# axiom_beta_interface_dummy_v0_13_r1_5_1a.net
KiCad netlist of a schematic drawn in EAGLE
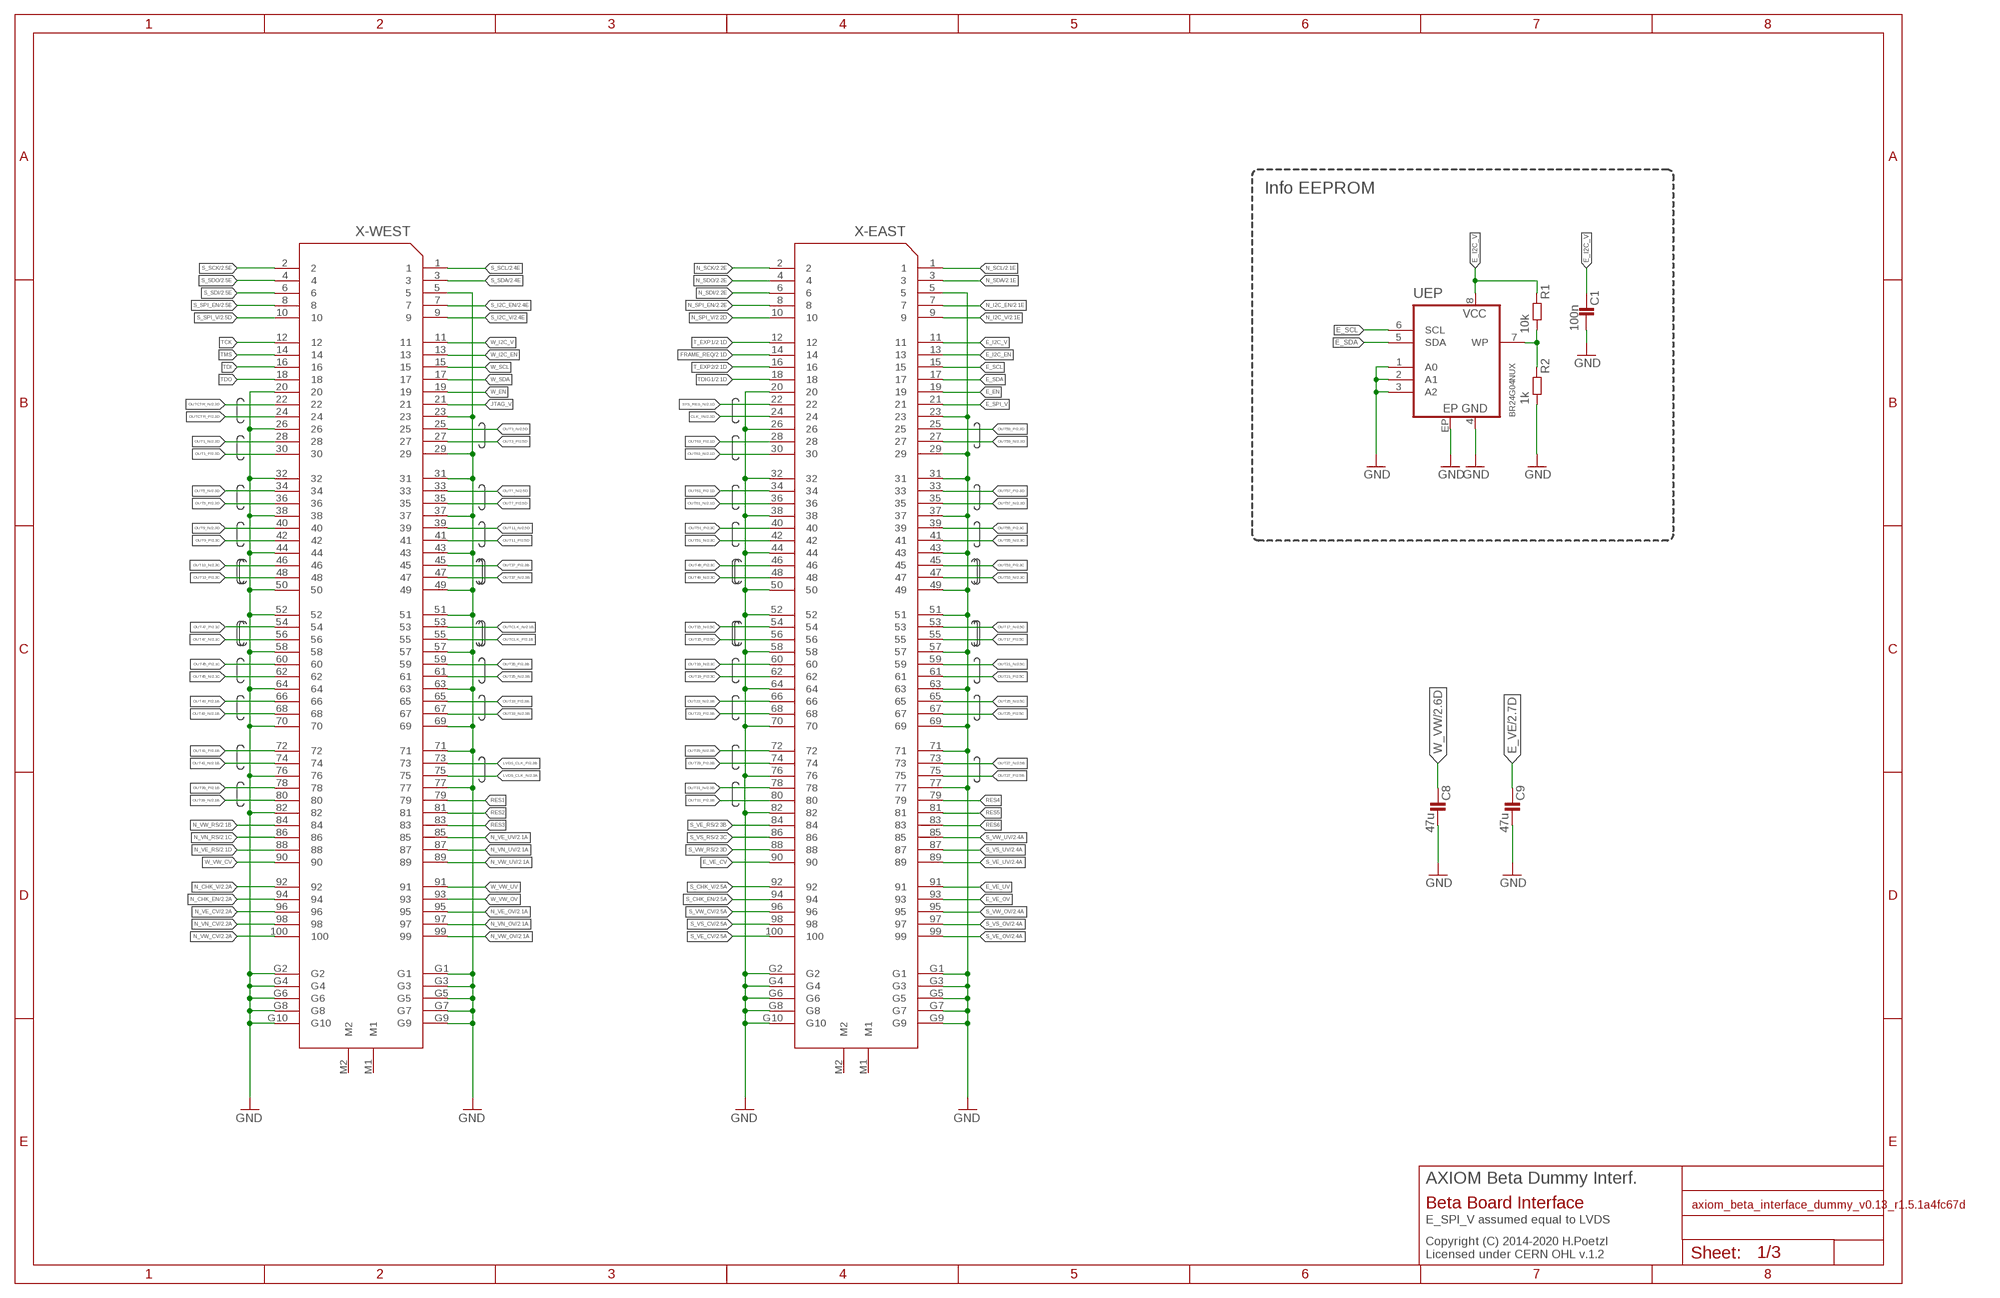
[diagram p0: schematic, sheet 1]
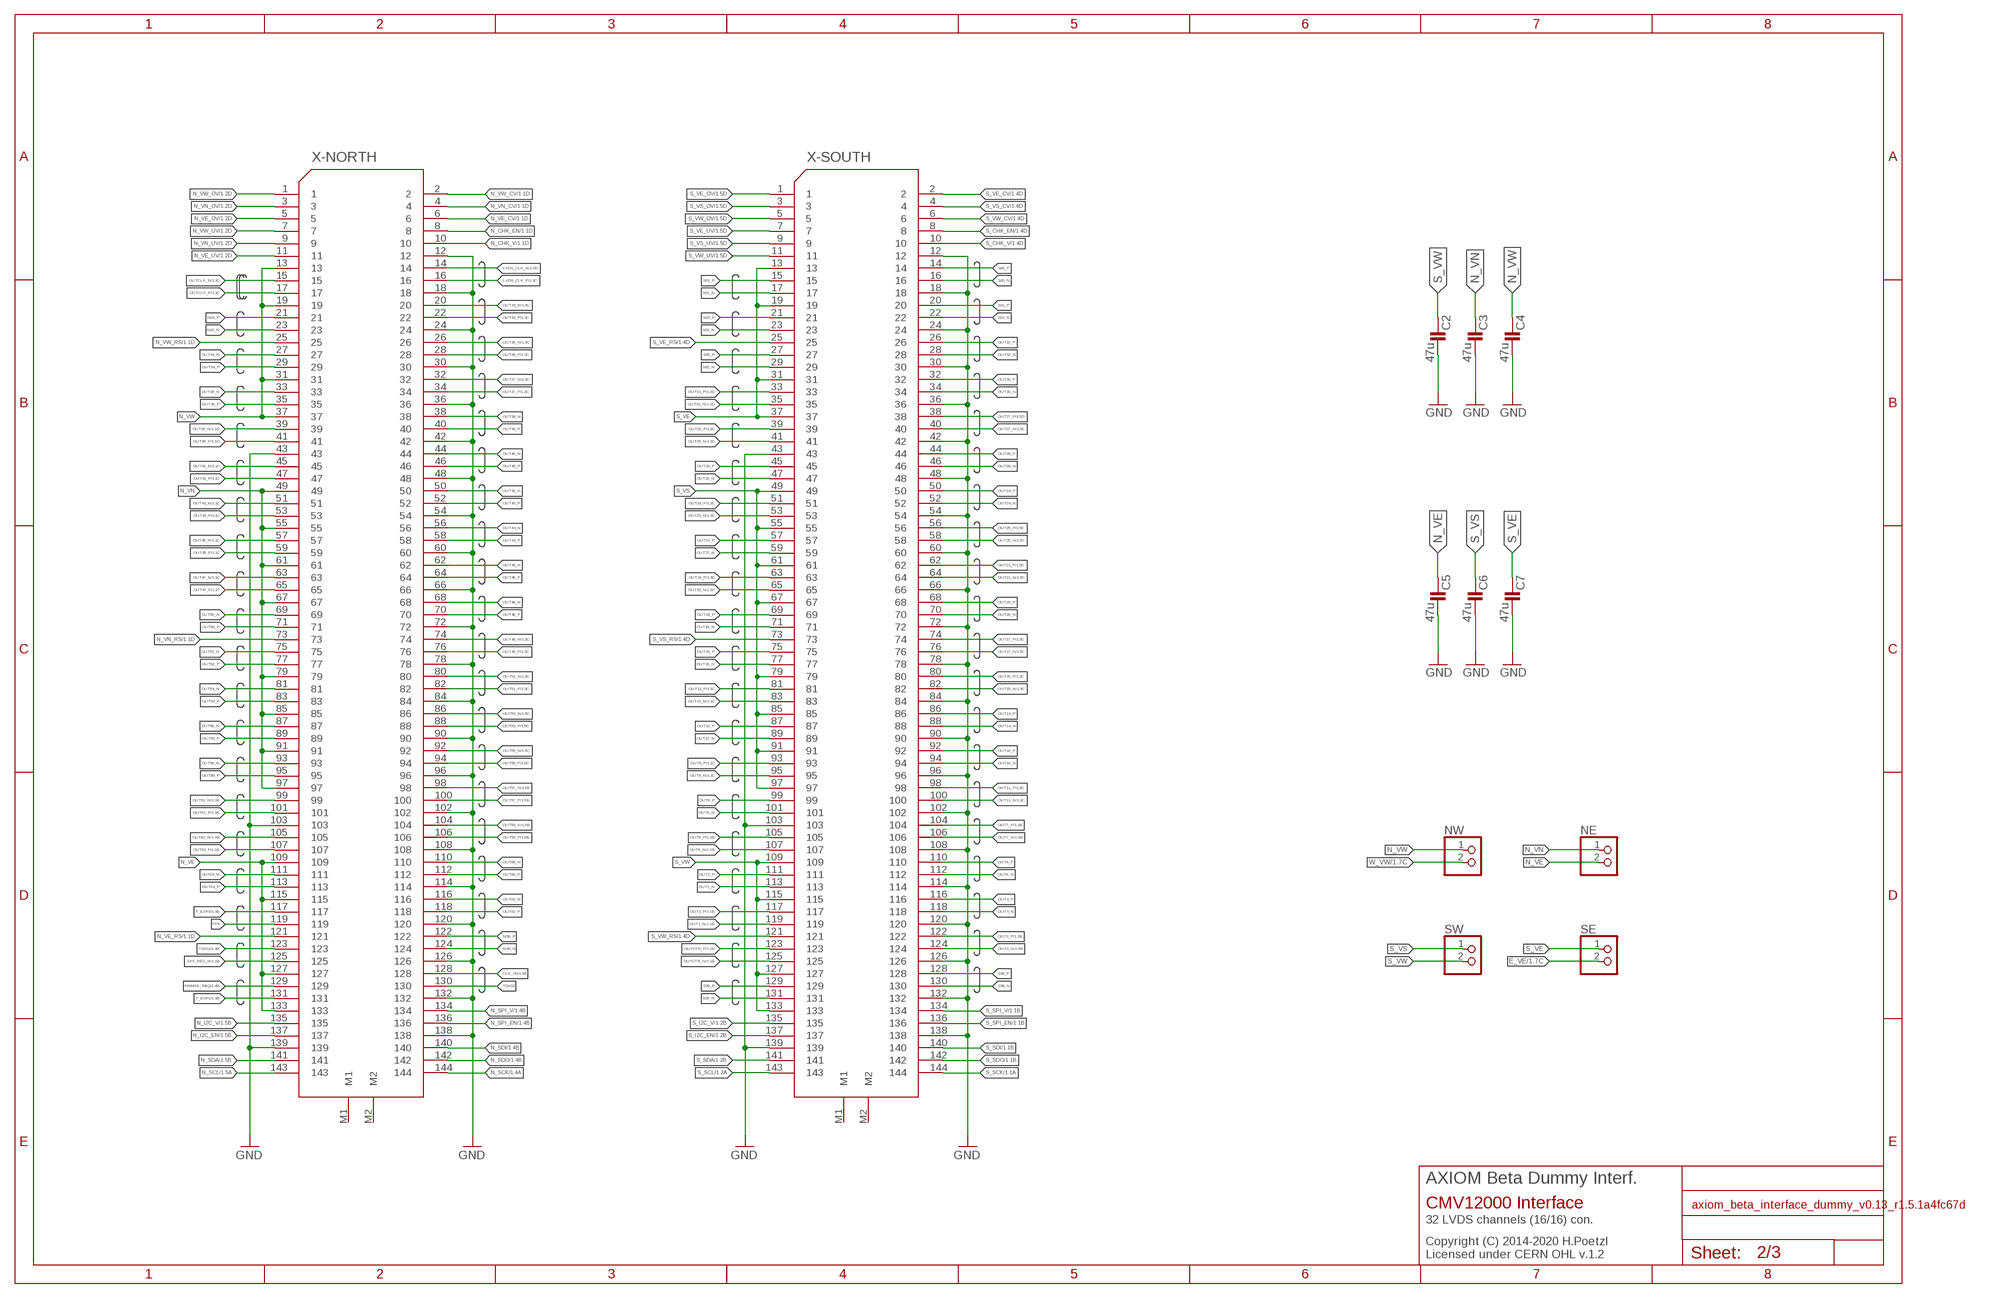
[diagram p1: schematic, sheet 2]
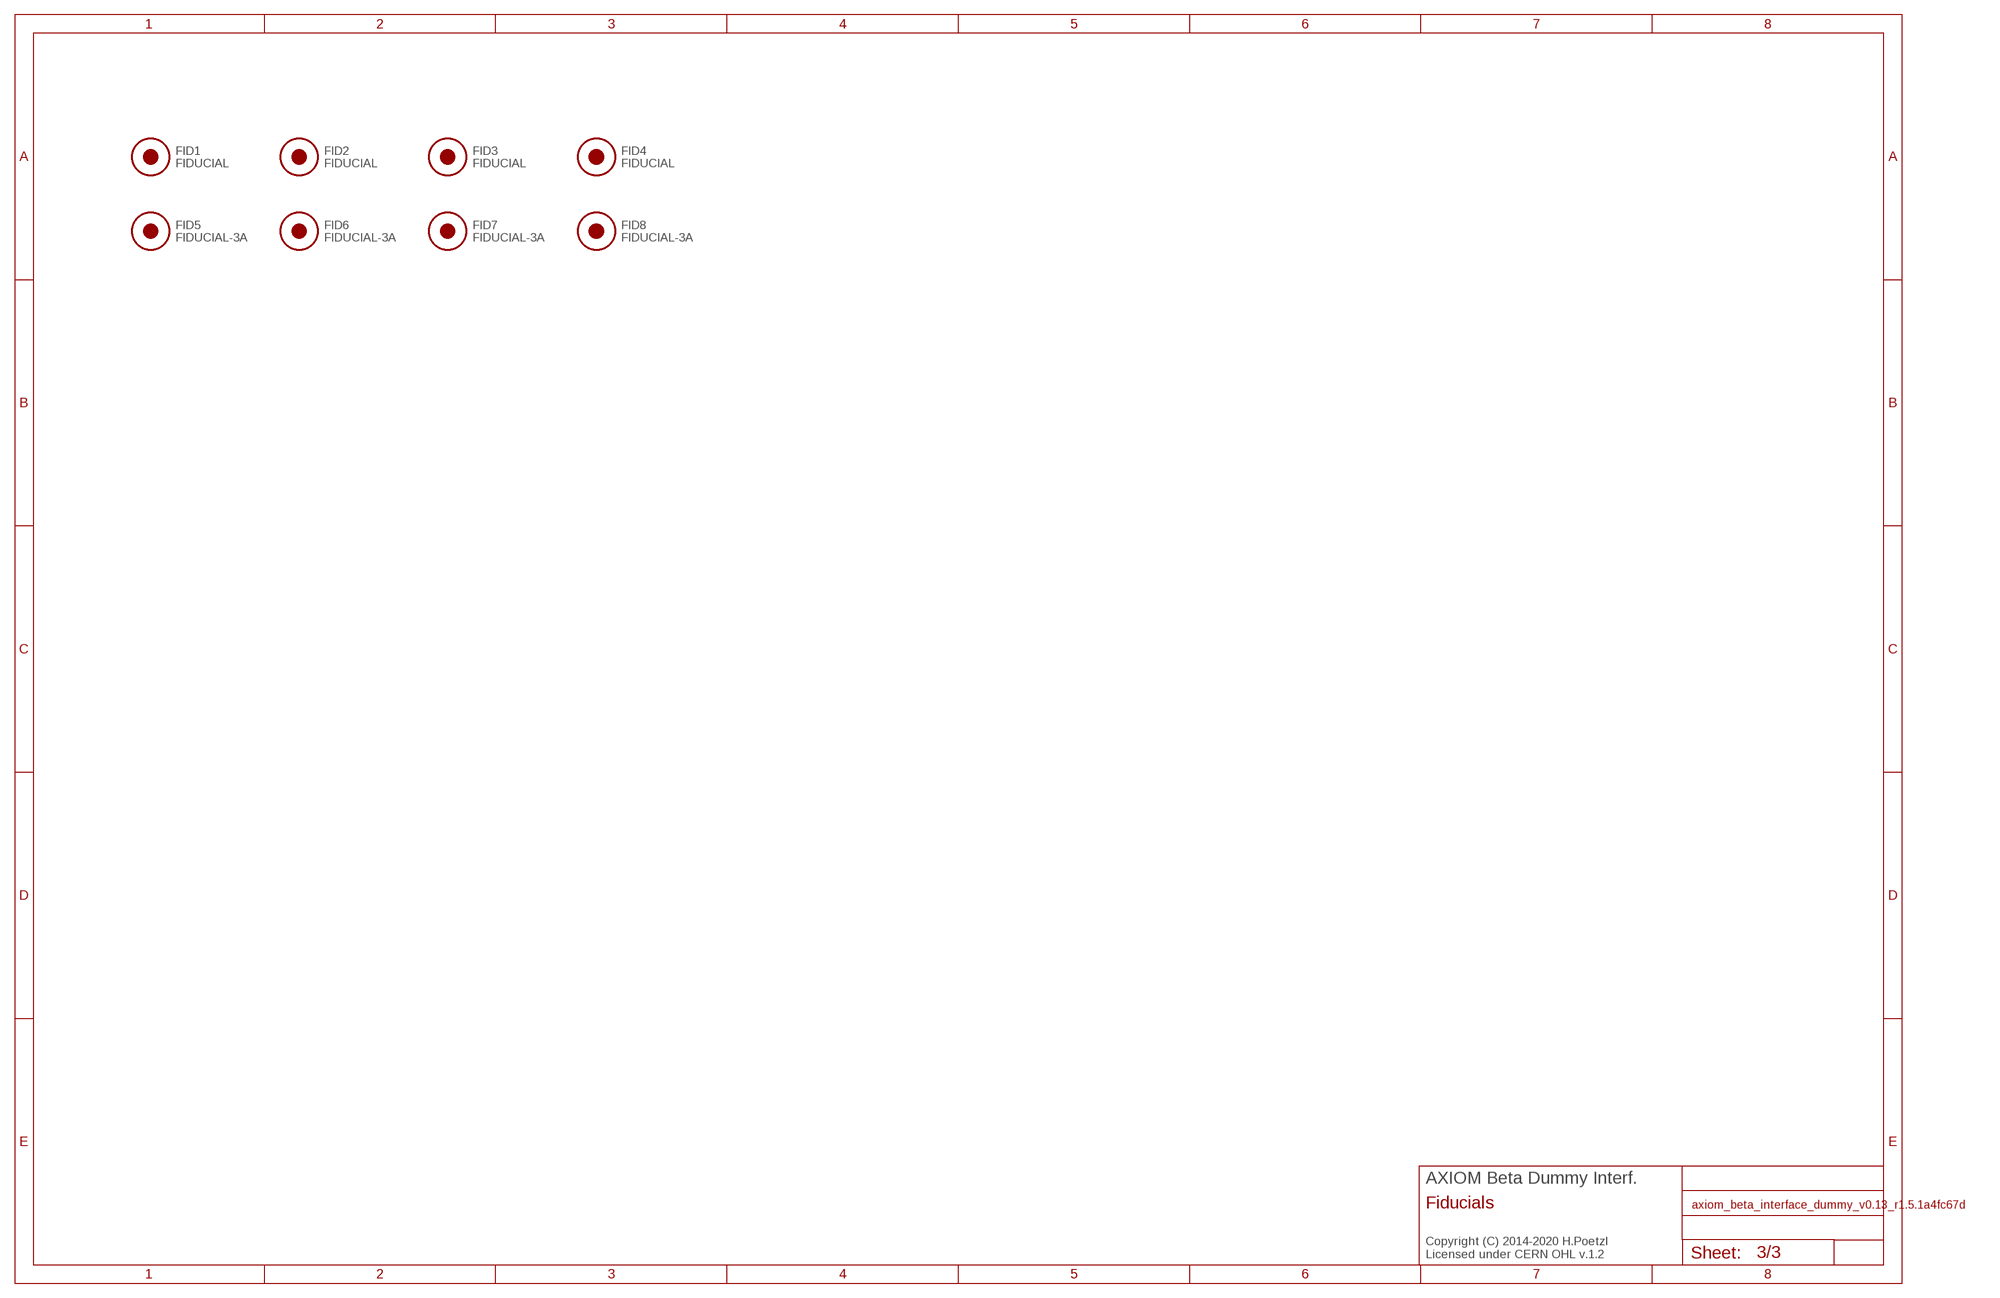
[diagram p2: schematic, sheet 3]

(export (version "E")
  (design (tool "Eeschema 10.0.6"))
  (components
    (comp (ref "FID1")
      (value "FIDUCIAL")
      (footprint "eagle-import:FID_ARROW")
      (libsource (lib "eagle-import") (part "FIDUCIAL"))
    )
    (comp (ref "FID2")
      (value "FIDUCIAL")
      (footprint "eagle-import:FID_ARROW")
      (libsource (lib "eagle-import") (part "FIDUCIAL"))
    )
    (comp (ref "FID3")
      (value "FIDUCIAL")
      (footprint "eagle-import:FID_ARROW")
      (libsource (lib "eagle-import") (part "FIDUCIAL"))
    )
    (comp (ref "FID4")
      (value "FIDUCIAL")
      (footprint "eagle-import:FID_ARROW")
      (libsource (lib "eagle-import") (part "FIDUCIAL"))
    )
    (comp (ref "FID5")
      (value "FIDUCIAL-3A")
      (footprint "eagle-import:FID_3ARROW")
      (libsource (lib "eagle-import") (part "FIDUCIAL-3A"))
    )
    (comp (ref "FID6")
      (value "FIDUCIAL-3A")
      (footprint "eagle-import:FID_3ARROW")
      (libsource (lib "eagle-import") (part "FIDUCIAL-3A"))
    )
    (comp (ref "FID7")
      (value "FIDUCIAL-3A")
      (footprint "eagle-import:FID_3ARROW")
      (libsource (lib "eagle-import") (part "FIDUCIAL-3A"))
    )
    (comp (ref "FID8")
      (value "FIDUCIAL-3A")
      (footprint "eagle-import:FID_3ARROW")
      (libsource (lib "eagle-import") (part "FIDUCIAL-3A"))
    )
    (comp (ref "C2")
      (value "47u")
      (footprint "eagle-import:0805-B")
      (libsource (lib "eagle-import") (part "C0805-B"))
    )
    (comp (ref "C3")
      (value "47u")
      (footprint "eagle-import:0805-B")
      (libsource (lib "eagle-import") (part "C0805-B"))
    )
    (comp (ref "C4")
      (value "47u")
      (footprint "eagle-import:0805-B")
      (libsource (lib "eagle-import") (part "C0805-B"))
    )
    (comp (ref "C5")
      (value "47u")
      (footprint "eagle-import:0805-B")
      (libsource (lib "eagle-import") (part "C0805-B"))
    )
    (comp (ref "C6")
      (value "47u")
      (footprint "eagle-import:0805-B")
      (libsource (lib "eagle-import") (part "C0805-B"))
    )
    (comp (ref "C7")
      (value "47u")
      (footprint "eagle-import:0805-B")
      (libsource (lib "eagle-import") (part "C0805-B"))
    )
    (comp (ref "NE")
      (value "PINHD-1X02_2.54")
      (footprint "eagle-import:1X02")
      (libsource (lib "eagle-import") (part "PINHD-1X02_2.54"))
    )
    (comp (ref "NW")
      (value "PINHD-1X02_2.54")
      (footprint "eagle-import:1X02")
      (libsource (lib "eagle-import") (part "PINHD-1X02_2.54"))
    )
    (comp (ref "SE")
      (value "PINHD-1X02_2.54")
      (footprint "eagle-import:1X02")
      (libsource (lib "eagle-import") (part "PINHD-1X02_2.54"))
    )
    (comp (ref "SW")
      (value "PINHD-1X02_2.54")
      (footprint "eagle-import:1X02")
      (libsource (lib "eagle-import") (part "PINHD-1X02_2.54"))
    )
    (comp (ref "X-NORTH")
      (value "FX10-144S")
      (footprint "eagle-import:FX10A-144S")
      (libsource (lib "eagle-import") (part "FX10-144S"))
    )
    (comp (ref "X-SOUTH")
      (value "FX10-144S")
      (footprint "eagle-import:FX10A-144S")
      (libsource (lib "eagle-import") (part "FX10-144S"))
    )
    (comp (ref "C1")
      (value "100n")
      (footprint "eagle-import:0402-B")
      (libsource (lib "eagle-import") (part "C0402-B"))
    )
    (comp (ref "C8")
      (value "47u")
      (footprint "eagle-import:0805-B")
      (libsource (lib "eagle-import") (part "C0805-B"))
    )
    (comp (ref "C9")
      (value "47u")
      (footprint "eagle-import:0805-B")
      (libsource (lib "eagle-import") (part "C0805-B"))
    )
    (comp (ref "R1")
      (value "10k")
      (footprint "eagle-import:0402-B")
      (libsource (lib "eagle-import") (part "R0402-B"))
    )
    (comp (ref "R2")
      (value "1k")
      (footprint "eagle-import:0402-B")
      (libsource (lib "eagle-import") (part "R0402-B"))
    )
    (comp (ref "UEP")
      (value "BR24G04NUX")
      (footprint "eagle-import:DFN200X300X100-9N")
      (libsource (lib "eagle-import") (part "BR24G04NUX"))
    )
    (comp (ref "X-EAST")
      (value "FX10-100/10P")
      (footprint "eagle-import:FX10A-100P_10")
      (libsource (lib "eagle-import") (part "FX10-100/10P"))
    )
    (comp (ref "X-WEST")
      (value "FX10-100/10P")
      (footprint "eagle-import:FX10A-100P_10")
      (libsource (lib "eagle-import") (part "FX10-100/10P"))
    )
  )
  (nets
    (net (code "1") (name "CLK_IN") (class "Default")
      (node (ref "X-EAST") (pin "24") (pinfunction "24_24") (pintype "bidirectional"))
      (node (ref "X-NORTH") (pin "128") (pinfunction "128_128") (pintype "bidirectional"))
    )
    (net (code "2") (name "E_EN") (class "Default")
      (node (ref "X-EAST") (pin "19") (pinfunction "19_19") (pintype "bidirectional"))
    )
    (net (code "3") (name "E_I2C_EN") (class "Default")
      (node (ref "X-EAST") (pin "13") (pinfunction "13_13") (pintype "bidirectional"))
    )
    (net (code "4") (name "E_I2C_V") (class "Default")
      (node (ref "C1") (pin "1") (pinfunction "1_1") (pintype "passive"))
      (node (ref "R1") (pin "1") (pinfunction "1_1") (pintype "passive"))
      (node (ref "UEP") (pin "8") (pinfunction "VCC_8") (pintype "power_in"))
      (node (ref "X-EAST") (pin "11") (pinfunction "11_11") (pintype "bidirectional"))
    )
    (net (code "5") (name "E_SCL") (class "Default")
      (node (ref "UEP") (pin "6") (pinfunction "SCL_6") (pintype "input"))
      (node (ref "X-EAST") (pin "15") (pinfunction "15_15") (pintype "bidirectional"))
    )
    (net (code "6") (name "E_SDA") (class "Default")
      (node (ref "UEP") (pin "5") (pinfunction "SDA_5") (pintype "bidirectional"))
      (node (ref "X-EAST") (pin "17") (pinfunction "17_17") (pintype "bidirectional"))
    )
    (net (code "7") (name "E_SPI_V") (class "Default")
      (node (ref "X-EAST") (pin "21") (pinfunction "21_21") (pintype "bidirectional"))
    )
    (net (code "8") (name "E_VE") (class "Default")
      (node (ref "C9") (pin "1") (pinfunction "1_1") (pintype "passive"))
      (node (ref "SE") (pin "2") (pinfunction "2_2") (pintype "passive"))
    )
    (net (code "9") (name "E_VE_CV") (class "Default")
      (node (ref "X-EAST") (pin "90") (pinfunction "90_90") (pintype "bidirectional"))
    )
    (net (code "10") (name "E_VE_OV") (class "Default")
      (node (ref "X-EAST") (pin "93") (pinfunction "93_93") (pintype "bidirectional"))
    )
    (net (code "11") (name "E_VE_UV") (class "Default")
      (node (ref "X-EAST") (pin "91") (pinfunction "91_91") (pintype "bidirectional"))
    )
    (net (code "12") (name "FRAME_REQ") (class "Default")
      (node (ref "X-EAST") (pin "14") (pinfunction "14_14") (pintype "bidirectional"))
      (node (ref "X-NORTH") (pin "129") (pinfunction "129_129") (pintype "bidirectional"))
    )
    (net (code "13") (name "GND") (class "Default")
      (node (ref "C1") (pin "2") (pinfunction "2_2") (pintype "passive"))
      (node (ref "C2") (pin "2") (pinfunction "2_2") (pintype "passive"))
      (node (ref "C3") (pin "2") (pinfunction "2_2") (pintype "passive"))
      (node (ref "C4") (pin "2") (pinfunction "2_2") (pintype "passive"))
      (node (ref "C5") (pin "2") (pinfunction "2_2") (pintype "passive"))
      (node (ref "C6") (pin "2") (pinfunction "2_2") (pintype "passive"))
      (node (ref "C7") (pin "2") (pinfunction "2_2") (pintype "passive"))
      (node (ref "C8") (pin "2") (pinfunction "2_2") (pintype "passive"))
      (node (ref "C9") (pin "2") (pinfunction "2_2") (pintype "passive"))
      (node (ref "R2") (pin "2") (pinfunction "2_2") (pintype "passive"))
      (node (ref "UEP") (pin "1") (pinfunction "A0_1") (pintype "input"))
      (node (ref "UEP") (pin "2") (pinfunction "A1_2") (pintype "input"))
      (node (ref "UEP") (pin "3") (pinfunction "A2_3") (pintype "input"))
      (node (ref "UEP") (pin "4") (pinfunction "GND_4") (pintype "passive"))
      (node (ref "UEP") (pin "EP") (pinfunction "EP_EP") (pintype "passive"))
      (node (ref "X-EAST") (pin "20") (pinfunction "20_20") (pintype "bidirectional"))
      (node (ref "X-EAST") (pin "23") (pinfunction "23_23") (pintype "bidirectional"))
      (node (ref "X-EAST") (pin "26") (pinfunction "26_26") (pintype "bidirectional"))
      (node (ref "X-EAST") (pin "29") (pinfunction "29_29") (pintype "bidirectional"))
      (node (ref "X-EAST") (pin "31") (pinfunction "31_31") (pintype "bidirectional"))
      (node (ref "X-EAST") (pin "32") (pinfunction "32_32") (pintype "bidirectional"))
      (node (ref "X-EAST") (pin "37") (pinfunction "37_37") (pintype "bidirectional"))
      (node (ref "X-EAST") (pin "38") (pinfunction "38_38") (pintype "bidirectional"))
      (node (ref "X-EAST") (pin "43") (pinfunction "43_43") (pintype "bidirectional"))
      (node (ref "X-EAST") (pin "44") (pinfunction "44_44") (pintype "bidirectional"))
      (node (ref "X-EAST") (pin "49") (pinfunction "49_49") (pintype "bidirectional"))
      (node (ref "X-EAST") (pin "5") (pinfunction "5_5") (pintype "bidirectional"))
      (node (ref "X-EAST") (pin "50") (pinfunction "50_50") (pintype "bidirectional"))
      (node (ref "X-EAST") (pin "51") (pinfunction "51_51") (pintype "bidirectional"))
      (node (ref "X-EAST") (pin "52") (pinfunction "52_52") (pintype "bidirectional"))
      (node (ref "X-EAST") (pin "57") (pinfunction "57_57") (pintype "bidirectional"))
      (node (ref "X-EAST") (pin "58") (pinfunction "58_58") (pintype "bidirectional"))
      (node (ref "X-EAST") (pin "63") (pinfunction "63_63") (pintype "bidirectional"))
      (node (ref "X-EAST") (pin "64") (pinfunction "64_64") (pintype "bidirectional"))
      (node (ref "X-EAST") (pin "69") (pinfunction "69_69") (pintype "bidirectional"))
      (node (ref "X-EAST") (pin "70") (pinfunction "70_70") (pintype "bidirectional"))
      (node (ref "X-EAST") (pin "71") (pinfunction "71_71") (pintype "bidirectional"))
      (node (ref "X-EAST") (pin "76") (pinfunction "76_76") (pintype "bidirectional"))
      (node (ref "X-EAST") (pin "77") (pinfunction "77_77") (pintype "bidirectional"))
      (node (ref "X-EAST") (pin "82") (pinfunction "82_82") (pintype "bidirectional"))
      (node (ref "X-EAST") (pin "G1") (pinfunction "G1_G1") (pintype "bidirectional"))
      (node (ref "X-EAST") (pin "G10") (pinfunction "G10_G10") (pintype "bidirectional"))
      (node (ref "X-EAST") (pin "G2") (pinfunction "G2_G2") (pintype "bidirectional"))
      (node (ref "X-EAST") (pin "G3") (pinfunction "G3_G3") (pintype "bidirectional"))
      (node (ref "X-EAST") (pin "G4") (pinfunction "G4_G4") (pintype "bidirectional"))
      (node (ref "X-EAST") (pin "G5") (pinfunction "G5_G5") (pintype "bidirectional"))
      (node (ref "X-EAST") (pin "G6") (pinfunction "G6_G6") (pintype "bidirectional"))
      (node (ref "X-EAST") (pin "G7") (pinfunction "G7_G7") (pintype "bidirectional"))
      (node (ref "X-EAST") (pin "G8") (pinfunction "G8_G8") (pintype "bidirectional"))
      (node (ref "X-EAST") (pin "G9") (pinfunction "G9_G9") (pintype "bidirectional"))
      (node (ref "X-NORTH") (pin "102") (pinfunction "102_102") (pintype "bidirectional"))
      (node (ref "X-NORTH") (pin "103") (pinfunction "103_103") (pintype "bidirectional"))
      (node (ref "X-NORTH") (pin "108") (pinfunction "108_108") (pintype "bidirectional"))
      (node (ref "X-NORTH") (pin "114") (pinfunction "114_114") (pintype "bidirectional"))
      (node (ref "X-NORTH") (pin "12") (pinfunction "12_12") (pintype "bidirectional"))
      (node (ref "X-NORTH") (pin "120") (pinfunction "120_120") (pintype "bidirectional"))
      (node (ref "X-NORTH") (pin "126") (pinfunction "126_126") (pintype "bidirectional"))
      (node (ref "X-NORTH") (pin "132") (pinfunction "132_132") (pintype "bidirectional"))
      (node (ref "X-NORTH") (pin "138") (pinfunction "138_138") (pintype "bidirectional"))
      (node (ref "X-NORTH") (pin "139") (pinfunction "139_139") (pintype "bidirectional"))
      (node (ref "X-NORTH") (pin "18") (pinfunction "18_18") (pintype "bidirectional"))
      (node (ref "X-NORTH") (pin "24") (pinfunction "24_24") (pintype "bidirectional"))
      (node (ref "X-NORTH") (pin "30") (pinfunction "30_30") (pintype "bidirectional"))
      (node (ref "X-NORTH") (pin "36") (pinfunction "36_36") (pintype "bidirectional"))
      (node (ref "X-NORTH") (pin "42") (pinfunction "42_42") (pintype "bidirectional"))
      (node (ref "X-NORTH") (pin "43") (pinfunction "43_43") (pintype "bidirectional"))
      (node (ref "X-NORTH") (pin "48") (pinfunction "48_48") (pintype "bidirectional"))
      (node (ref "X-NORTH") (pin "54") (pinfunction "54_54") (pintype "bidirectional"))
      (node (ref "X-NORTH") (pin "60") (pinfunction "60_60") (pintype "bidirectional"))
      (node (ref "X-NORTH") (pin "66") (pinfunction "66_66") (pintype "bidirectional"))
      (node (ref "X-NORTH") (pin "72") (pinfunction "72_72") (pintype "bidirectional"))
      (node (ref "X-NORTH") (pin "78") (pinfunction "78_78") (pintype "bidirectional"))
      (node (ref "X-NORTH") (pin "84") (pinfunction "84_84") (pintype "bidirectional"))
      (node (ref "X-NORTH") (pin "90") (pinfunction "90_90") (pintype "bidirectional"))
      (node (ref "X-NORTH") (pin "96") (pinfunction "96_96") (pintype "bidirectional"))
      (node (ref "X-SOUTH") (pin "102") (pinfunction "102_102") (pintype "bidirectional"))
      (node (ref "X-SOUTH") (pin "103") (pinfunction "103_103") (pintype "bidirectional"))
      (node (ref "X-SOUTH") (pin "108") (pinfunction "108_108") (pintype "bidirectional"))
      (node (ref "X-SOUTH") (pin "114") (pinfunction "114_114") (pintype "bidirectional"))
      (node (ref "X-SOUTH") (pin "12") (pinfunction "12_12") (pintype "bidirectional"))
      (node (ref "X-SOUTH") (pin "120") (pinfunction "120_120") (pintype "bidirectional"))
      (node (ref "X-SOUTH") (pin "126") (pinfunction "126_126") (pintype "bidirectional"))
      (node (ref "X-SOUTH") (pin "132") (pinfunction "132_132") (pintype "bidirectional"))
      (node (ref "X-SOUTH") (pin "138") (pinfunction "138_138") (pintype "bidirectional"))
      (node (ref "X-SOUTH") (pin "139") (pinfunction "139_139") (pintype "bidirectional"))
      (node (ref "X-SOUTH") (pin "18") (pinfunction "18_18") (pintype "bidirectional"))
      (node (ref "X-SOUTH") (pin "24") (pinfunction "24_24") (pintype "bidirectional"))
      (node (ref "X-SOUTH") (pin "30") (pinfunction "30_30") (pintype "bidirectional"))
      (node (ref "X-SOUTH") (pin "36") (pinfunction "36_36") (pintype "bidirectional"))
      (node (ref "X-SOUTH") (pin "42") (pinfunction "42_42") (pintype "bidirectional"))
      (node (ref "X-SOUTH") (pin "43") (pinfunction "43_43") (pintype "bidirectional"))
      (node (ref "X-SOUTH") (pin "48") (pinfunction "48_48") (pintype "bidirectional"))
      (node (ref "X-SOUTH") (pin "54") (pinfunction "54_54") (pintype "bidirectional"))
      (node (ref "X-SOUTH") (pin "60") (pinfunction "60_60") (pintype "bidirectional"))
      (node (ref "X-SOUTH") (pin "66") (pinfunction "66_66") (pintype "bidirectional"))
      (node (ref "X-SOUTH") (pin "72") (pinfunction "72_72") (pintype "bidirectional"))
      (node (ref "X-SOUTH") (pin "78") (pinfunction "78_78") (pintype "bidirectional"))
      (node (ref "X-SOUTH") (pin "84") (pinfunction "84_84") (pintype "bidirectional"))
      (node (ref "X-SOUTH") (pin "90") (pinfunction "90_90") (pintype "bidirectional"))
      (node (ref "X-SOUTH") (pin "96") (pinfunction "96_96") (pintype "bidirectional"))
      (node (ref "X-WEST") (pin "20") (pinfunction "20_20") (pintype "bidirectional"))
      (node (ref "X-WEST") (pin "23") (pinfunction "23_23") (pintype "bidirectional"))
      (node (ref "X-WEST") (pin "26") (pinfunction "26_26") (pintype "bidirectional"))
      (node (ref "X-WEST") (pin "29") (pinfunction "29_29") (pintype "bidirectional"))
      (node (ref "X-WEST") (pin "31") (pinfunction "31_31") (pintype "bidirectional"))
      (node (ref "X-WEST") (pin "32") (pinfunction "32_32") (pintype "bidirectional"))
      (node (ref "X-WEST") (pin "37") (pinfunction "37_37") (pintype "bidirectional"))
      (node (ref "X-WEST") (pin "38") (pinfunction "38_38") (pintype "bidirectional"))
      (node (ref "X-WEST") (pin "43") (pinfunction "43_43") (pintype "bidirectional"))
      (node (ref "X-WEST") (pin "44") (pinfunction "44_44") (pintype "bidirectional"))
      (node (ref "X-WEST") (pin "49") (pinfunction "49_49") (pintype "bidirectional"))
      (node (ref "X-WEST") (pin "5") (pinfunction "5_5") (pintype "bidirectional"))
      (node (ref "X-WEST") (pin "50") (pinfunction "50_50") (pintype "bidirectional"))
      (node (ref "X-WEST") (pin "51") (pinfunction "51_51") (pintype "bidirectional"))
      (node (ref "X-WEST") (pin "52") (pinfunction "52_52") (pintype "bidirectional"))
      (node (ref "X-WEST") (pin "57") (pinfunction "57_57") (pintype "bidirectional"))
      (node (ref "X-WEST") (pin "58") (pinfunction "58_58") (pintype "bidirectional"))
      (node (ref "X-WEST") (pin "63") (pinfunction "63_63") (pintype "bidirectional"))
      (node (ref "X-WEST") (pin "64") (pinfunction "64_64") (pintype "bidirectional"))
      (node (ref "X-WEST") (pin "69") (pinfunction "69_69") (pintype "bidirectional"))
      (node (ref "X-WEST") (pin "70") (pinfunction "70_70") (pintype "bidirectional"))
      (node (ref "X-WEST") (pin "71") (pinfunction "71_71") (pintype "bidirectional"))
      (node (ref "X-WEST") (pin "76") (pinfunction "76_76") (pintype "bidirectional"))
      (node (ref "X-WEST") (pin "77") (pinfunction "77_77") (pintype "bidirectional"))
      (node (ref "X-WEST") (pin "82") (pinfunction "82_82") (pintype "bidirectional"))
      (node (ref "X-WEST") (pin "G1") (pinfunction "G1_G1") (pintype "bidirectional"))
      (node (ref "X-WEST") (pin "G10") (pinfunction "G10_G10") (pintype "bidirectional"))
      (node (ref "X-WEST") (pin "G2") (pinfunction "G2_G2") (pintype "bidirectional"))
      (node (ref "X-WEST") (pin "G3") (pinfunction "G3_G3") (pintype "bidirectional"))
      (node (ref "X-WEST") (pin "G4") (pinfunction "G4_G4") (pintype "bidirectional"))
      (node (ref "X-WEST") (pin "G5") (pinfunction "G5_G5") (pintype "bidirectional"))
      (node (ref "X-WEST") (pin "G6") (pinfunction "G6_G6") (pintype "bidirectional"))
      (node (ref "X-WEST") (pin "G7") (pinfunction "G7_G7") (pintype "bidirectional"))
      (node (ref "X-WEST") (pin "G8") (pinfunction "G8_G8") (pintype "bidirectional"))
      (node (ref "X-WEST") (pin "G9") (pinfunction "G9_G9") (pintype "bidirectional"))
    )
    (net (code "14") (name "JTAG_V") (class "Default")
      (node (ref "X-WEST") (pin "21") (pinfunction "21_21") (pintype "bidirectional"))
    )
    (net (code "15") (name "LVDS_CLK_N") (class "Default")
      (node (ref "X-NORTH") (pin "14") (pinfunction "14_14") (pintype "bidirectional"))
      (node (ref "X-WEST") (pin "75") (pinfunction "75_75") (pintype "bidirectional"))
    )
    (net (code "16") (name "LVDS_CLK_P") (class "Default")
      (node (ref "X-NORTH") (pin "16") (pinfunction "16_16") (pintype "bidirectional"))
      (node (ref "X-WEST") (pin "73") (pinfunction "73_73") (pintype "bidirectional"))
    )
    (net (code "17") (name "N03_N") (class "Default")
      (node (ref "X-NORTH") (pin "23") (pinfunction "23_23") (pintype "bidirectional"))
    )
    (net (code "18") (name "N03_P") (class "Default")
      (node (ref "X-NORTH") (pin "21") (pinfunction "21_21") (pintype "bidirectional"))
    )
    (net (code "19") (name "N36_N") (class "Default")
      (node (ref "X-NORTH") (pin "124") (pinfunction "124_124") (pintype "bidirectional"))
    )
    (net (code "20") (name "N36_P") (class "Default")
      (node (ref "X-NORTH") (pin "122") (pinfunction "122_122") (pintype "bidirectional"))
    )
    (net (code "21") (name "N_CHK_EN") (class "Default")
      (node (ref "X-NORTH") (pin "8") (pinfunction "8_8") (pintype "bidirectional"))
      (node (ref "X-WEST") (pin "94") (pinfunction "94_94") (pintype "bidirectional"))
    )
    (net (code "22") (name "N_CHK_V") (class "Default")
      (node (ref "X-NORTH") (pin "10") (pinfunction "10_10") (pintype "bidirectional"))
      (node (ref "X-WEST") (pin "92") (pinfunction "92_92") (pintype "bidirectional"))
    )
    (net (code "23") (name "N_I2C_EN") (class "Default")
      (node (ref "X-EAST") (pin "7") (pinfunction "7_7") (pintype "bidirectional"))
      (node (ref "X-NORTH") (pin "137") (pinfunction "137_137") (pintype "bidirectional"))
    )
    (net (code "24") (name "N_I2C_V") (class "Default")
      (node (ref "X-EAST") (pin "9") (pinfunction "9_9") (pintype "bidirectional"))
      (node (ref "X-NORTH") (pin "135") (pinfunction "135_135") (pintype "bidirectional"))
    )
    (net (code "25") (name "N_SCK") (class "Default")
      (node (ref "X-EAST") (pin "2") (pinfunction "2_2") (pintype "bidirectional"))
      (node (ref "X-NORTH") (pin "144") (pinfunction "144_144") (pintype "bidirectional"))
    )
    (net (code "26") (name "N_SCL") (class "Default")
      (node (ref "X-EAST") (pin "1") (pinfunction "1_1") (pintype "bidirectional"))
      (node (ref "X-NORTH") (pin "143") (pinfunction "143_143") (pintype "bidirectional"))
    )
    (net (code "27") (name "N_SDA") (class "Default")
      (node (ref "X-EAST") (pin "3") (pinfunction "3_3") (pintype "bidirectional"))
      (node (ref "X-NORTH") (pin "141") (pinfunction "141_141") (pintype "bidirectional"))
    )
    (net (code "28") (name "N_SDI") (class "Default")
      (node (ref "X-EAST") (pin "6") (pinfunction "6_6") (pintype "bidirectional"))
      (node (ref "X-NORTH") (pin "140") (pinfunction "140_140") (pintype "bidirectional"))
    )
    (net (code "29") (name "N_SDO") (class "Default")
      (node (ref "X-EAST") (pin "4") (pinfunction "4_4") (pintype "bidirectional"))
      (node (ref "X-NORTH") (pin "142") (pinfunction "142_142") (pintype "bidirectional"))
    )
    (net (code "30") (name "N_SPI_EN") (class "Default")
      (node (ref "X-EAST") (pin "8") (pinfunction "8_8") (pintype "bidirectional"))
      (node (ref "X-NORTH") (pin "136") (pinfunction "136_136") (pintype "bidirectional"))
    )
    (net (code "31") (name "N_SPI_V") (class "Default")
      (node (ref "X-EAST") (pin "10") (pinfunction "10_10") (pintype "bidirectional"))
      (node (ref "X-NORTH") (pin "134") (pinfunction "134_134") (pintype "bidirectional"))
    )
    (net (code "32") (name "N_VE") (class "Default")
      (node (ref "C5") (pin "1") (pinfunction "1_1") (pintype "passive"))
      (node (ref "NE") (pin "2") (pinfunction "2_2") (pintype "passive"))
      (node (ref "X-NORTH") (pin "109") (pinfunction "109_109") (pintype "bidirectional"))
      (node (ref "X-NORTH") (pin "115") (pinfunction "115_115") (pintype "bidirectional"))
      (node (ref "X-NORTH") (pin "127") (pinfunction "127_127") (pintype "bidirectional"))
      (node (ref "X-NORTH") (pin "133") (pinfunction "133_133") (pintype "bidirectional"))
    )
    (net (code "33") (name "N_VE_CV") (class "Default")
      (node (ref "X-NORTH") (pin "6") (pinfunction "6_6") (pintype "bidirectional"))
      (node (ref "X-WEST") (pin "96") (pinfunction "96_96") (pintype "bidirectional"))
    )
    (net (code "34") (name "N_VE_OV") (class "Default")
      (node (ref "X-NORTH") (pin "5") (pinfunction "5_5") (pintype "bidirectional"))
      (node (ref "X-WEST") (pin "95") (pinfunction "95_95") (pintype "bidirectional"))
    )
    (net (code "35") (name "N_VE_RS") (class "Default")
      (node (ref "X-NORTH") (pin "121") (pinfunction "121_121") (pintype "bidirectional"))
      (node (ref "X-WEST") (pin "88") (pinfunction "88_88") (pintype "bidirectional"))
    )
    (net (code "36") (name "N_VE_UV") (class "Default")
      (node (ref "X-NORTH") (pin "11") (pinfunction "11_11") (pintype "bidirectional"))
      (node (ref "X-WEST") (pin "85") (pinfunction "85_85") (pintype "bidirectional"))
    )
    (net (code "37") (name "N_VN") (class "Default")
      (node (ref "C3") (pin "1") (pinfunction "1_1") (pintype "passive"))
      (node (ref "NE") (pin "1") (pinfunction "1_1") (pintype "passive"))
      (node (ref "X-NORTH") (pin "49") (pinfunction "49_49") (pintype "bidirectional"))
      (node (ref "X-NORTH") (pin "55") (pinfunction "55_55") (pintype "bidirectional"))
      (node (ref "X-NORTH") (pin "61") (pinfunction "61_61") (pintype "bidirectional"))
      (node (ref "X-NORTH") (pin "67") (pinfunction "67_67") (pintype "bidirectional"))
      (node (ref "X-NORTH") (pin "79") (pinfunction "79_79") (pintype "bidirectional"))
      (node (ref "X-NORTH") (pin "85") (pinfunction "85_85") (pintype "bidirectional"))
      (node (ref "X-NORTH") (pin "91") (pinfunction "91_91") (pintype "bidirectional"))
      (node (ref "X-NORTH") (pin "97") (pinfunction "97_97") (pintype "bidirectional"))
    )
    (net (code "38") (name "N_VN_CV") (class "Default")
      (node (ref "X-NORTH") (pin "4") (pinfunction "4_4") (pintype "bidirectional"))
      (node (ref "X-WEST") (pin "98") (pinfunction "98_98") (pintype "bidirectional"))
    )
    (net (code "39") (name "N_VN_OV") (class "Default")
      (node (ref "X-NORTH") (pin "3") (pinfunction "3_3") (pintype "bidirectional"))
      (node (ref "X-WEST") (pin "97") (pinfunction "97_97") (pintype "bidirectional"))
    )
    (net (code "40") (name "N_VN_RS") (class "Default")
      (node (ref "X-NORTH") (pin "73") (pinfunction "73_73") (pintype "bidirectional"))
      (node (ref "X-WEST") (pin "86") (pinfunction "86_86") (pintype "bidirectional"))
    )
    (net (code "41") (name "N_VN_UV") (class "Default")
      (node (ref "X-NORTH") (pin "9") (pinfunction "9_9") (pintype "bidirectional"))
      (node (ref "X-WEST") (pin "87") (pinfunction "87_87") (pintype "bidirectional"))
    )
    (net (code "42") (name "N_VW") (class "Default")
      (node (ref "C4") (pin "1") (pinfunction "1_1") (pintype "passive"))
      (node (ref "NW") (pin "1") (pinfunction "1_1") (pintype "passive"))
      (node (ref "X-NORTH") (pin "13") (pinfunction "13_13") (pintype "bidirectional"))
      (node (ref "X-NORTH") (pin "19") (pinfunction "19_19") (pintype "bidirectional"))
      (node (ref "X-NORTH") (pin "31") (pinfunction "31_31") (pintype "bidirectional"))
      (node (ref "X-NORTH") (pin "37") (pinfunction "37_37") (pintype "bidirectional"))
    )
    (net (code "43") (name "N_VW_CV") (class "Default")
      (node (ref "X-NORTH") (pin "2") (pinfunction "2_2") (pintype "bidirectional"))
      (node (ref "X-WEST") (pin "100") (pinfunction "100_100") (pintype "bidirectional"))
    )
    (net (code "44") (name "N_VW_OV") (class "Default")
      (node (ref "X-NORTH") (pin "1") (pinfunction "1_1") (pintype "bidirectional"))
      (node (ref "X-WEST") (pin "99") (pinfunction "99_99") (pintype "bidirectional"))
    )
    (net (code "45") (name "N_VW_RS") (class "Default")
      (node (ref "X-NORTH") (pin "25") (pinfunction "25_25") (pintype "bidirectional"))
      (node (ref "X-WEST") (pin "84") (pinfunction "84_84") (pintype "bidirectional"))
    )
    (net (code "46") (name "N_VW_UV") (class "Default")
      (node (ref "X-NORTH") (pin "7") (pinfunction "7_7") (pintype "bidirectional"))
      (node (ref "X-WEST") (pin "89") (pinfunction "89_89") (pintype "bidirectional"))
    )
    (net (code "47") (name "Net-(UEP-WP)") (class "Default")
      (node (ref "R1") (pin "2") (pinfunction "2_2") (pintype "passive"))
      (node (ref "R2") (pin "1") (pinfunction "1_1") (pintype "passive"))
      (node (ref "UEP") (pin "7") (pinfunction "WP_7") (pintype "input"))
    )
    (net (code "48") (name "OUT1_N") (class "Default")
      (node (ref "X-SOUTH") (pin "119") (pinfunction "119_119") (pintype "bidirectional"))
      (node (ref "X-WEST") (pin "28") (pinfunction "28_28") (pintype "bidirectional"))
    )
    (net (code "49") (name "OUT1_P") (class "Default")
      (node (ref "X-SOUTH") (pin "117") (pinfunction "117_117") (pintype "bidirectional"))
      (node (ref "X-WEST") (pin "30") (pinfunction "30_30") (pintype "bidirectional"))
    )
    (net (code "50") (name "OUT2_N") (class "Default")
      (node (ref "X-SOUTH") (pin "113") (pinfunction "113_113") (pintype "bidirectional"))
    )
    (net (code "51") (name "OUT2_P") (class "Default")
      (node (ref "X-SOUTH") (pin "111") (pinfunction "111_111") (pintype "bidirectional"))
    )
    (net (code "52") (name "OUT3_N") (class "Default")
      (node (ref "X-SOUTH") (pin "124") (pinfunction "124_124") (pintype "bidirectional"))
      (node (ref "X-WEST") (pin "25") (pinfunction "25_25") (pintype "bidirectional"))
    )
    (net (code "53") (name "OUT3_P") (class "Default")
      (node (ref "X-SOUTH") (pin "122") (pinfunction "122_122") (pintype "bidirectional"))
      (node (ref "X-WEST") (pin "27") (pinfunction "27_27") (pintype "bidirectional"))
    )
    (net (code "54") (name "OUT4_N") (class "Default")
      (node (ref "X-SOUTH") (pin "118") (pinfunction "118_118") (pintype "bidirectional"))
    )
    (net (code "55") (name "OUT4_P") (class "Default")
      (node (ref "X-SOUTH") (pin "116") (pinfunction "116_116") (pintype "bidirectional"))
    )
    (net (code "56") (name "OUT5_N") (class "Default")
      (node (ref "X-SOUTH") (pin "107") (pinfunction "107_107") (pintype "bidirectional"))
      (node (ref "X-WEST") (pin "34") (pinfunction "34_34") (pintype "bidirectional"))
    )
    (net (code "57") (name "OUT5_P") (class "Default")
      (node (ref "X-SOUTH") (pin "105") (pinfunction "105_105") (pintype "bidirectional"))
      (node (ref "X-WEST") (pin "36") (pinfunction "36_36") (pintype "bidirectional"))
    )
    (net (code "58") (name "OUT6_N") (class "Default")
      (node (ref "X-SOUTH") (pin "112") (pinfunction "112_112") (pintype "bidirectional"))
    )
    (net (code "59") (name "OUT6_P") (class "Default")
      (node (ref "X-SOUTH") (pin "110") (pinfunction "110_110") (pintype "bidirectional"))
    )
    (net (code "60") (name "OUT7_N") (class "Default")
      (node (ref "X-SOUTH") (pin "106") (pinfunction "106_106") (pintype "bidirectional"))
      (node (ref "X-WEST") (pin "33") (pinfunction "33_33") (pintype "bidirectional"))
    )
    (net (code "61") (name "OUT7_P") (class "Default")
      (node (ref "X-SOUTH") (pin "104") (pinfunction "104_104") (pintype "bidirectional"))
      (node (ref "X-WEST") (pin "35") (pinfunction "35_35") (pintype "bidirectional"))
    )
    (net (code "62") (name "OUT8_N") (class "Default")
      (node (ref "X-SOUTH") (pin "101") (pinfunction "101_101") (pintype "bidirectional"))
    )
    (net (code "63") (name "OUT8_P") (class "Default")
      (node (ref "X-SOUTH") (pin "99") (pinfunction "99_99") (pintype "bidirectional"))
    )
    (net (code "64") (name "OUT9_N") (class "Default")
      (node (ref "X-SOUTH") (pin "95") (pinfunction "95_95") (pintype "bidirectional"))
      (node (ref "X-WEST") (pin "40") (pinfunction "40_40") (pintype "bidirectional"))
    )
    (net (code "65") (name "OUT9_P") (class "Default")
      (node (ref "X-SOUTH") (pin "93") (pinfunction "93_93") (pintype "bidirectional"))
      (node (ref "X-WEST") (pin "42") (pinfunction "42_42") (pintype "bidirectional"))
    )
    (net (code "66") (name "OUT10_N") (class "Default")
      (node (ref "X-SOUTH") (pin "94") (pinfunction "94_94") (pintype "bidirectional"))
    )
    (net (code "67") (name "OUT10_P") (class "Default")
      (node (ref "X-SOUTH") (pin "92") (pinfunction "92_92") (pintype "bidirectional"))
    )
    (net (code "68") (name "OUT11_N") (class "Default")
      (node (ref "X-SOUTH") (pin "100") (pinfunction "100_100") (pintype "bidirectional"))
      (node (ref "X-WEST") (pin "39") (pinfunction "39_39") (pintype "bidirectional"))
    )
    (net (code "69") (name "OUT11_P") (class "Default")
      (node (ref "X-SOUTH") (pin "98") (pinfunction "98_98") (pintype "bidirectional"))
      (node (ref "X-WEST") (pin "41") (pinfunction "41_41") (pintype "bidirectional"))
    )
    (net (code "70") (name "OUT12_N") (class "Default")
      (node (ref "X-SOUTH") (pin "89") (pinfunction "89_89") (pintype "bidirectional"))
    )
    (net (code "71") (name "OUT12_P") (class "Default")
      (node (ref "X-SOUTH") (pin "87") (pinfunction "87_87") (pintype "bidirectional"))
    )
    (net (code "72") (name "OUT13_N") (class "Default")
      (node (ref "X-SOUTH") (pin "83") (pinfunction "83_83") (pintype "bidirectional"))
      (node (ref "X-WEST") (pin "46") (pinfunction "46_46") (pintype "bidirectional"))
    )
    (net (code "73") (name "OUT13_P") (class "Default")
      (node (ref "X-SOUTH") (pin "81") (pinfunction "81_81") (pintype "bidirectional"))
      (node (ref "X-WEST") (pin "48") (pinfunction "48_48") (pintype "bidirectional"))
    )
    (net (code "74") (name "OUT14_N") (class "Default")
      (node (ref "X-SOUTH") (pin "88") (pinfunction "88_88") (pintype "bidirectional"))
    )
    (net (code "75") (name "OUT14_P") (class "Default")
      (node (ref "X-SOUTH") (pin "86") (pinfunction "86_86") (pintype "bidirectional"))
    )
    (net (code "76") (name "OUT15_N") (class "Default")
      (node (ref "X-EAST") (pin "54") (pinfunction "54_54") (pintype "bidirectional"))
      (node (ref "X-SOUTH") (pin "82") (pinfunction "82_82") (pintype "bidirectional"))
    )
    (net (code "77") (name "OUT15_P") (class "Default")
      (node (ref "X-EAST") (pin "56") (pinfunction "56_56") (pintype "bidirectional"))
      (node (ref "X-SOUTH") (pin "80") (pinfunction "80_80") (pintype "bidirectional"))
    )
    (net (code "78") (name "OUT16_N") (class "Default")
      (node (ref "X-SOUTH") (pin "77") (pinfunction "77_77") (pintype "bidirectional"))
    )
    (net (code "79") (name "OUT16_P") (class "Default")
      (node (ref "X-SOUTH") (pin "75") (pinfunction "75_75") (pintype "bidirectional"))
    )
    (net (code "80") (name "OUT17_N") (class "Default")
      (node (ref "X-EAST") (pin "53") (pinfunction "53_53") (pintype "bidirectional"))
      (node (ref "X-SOUTH") (pin "76") (pinfunction "76_76") (pintype "bidirectional"))
    )
    (net (code "81") (name "OUT17_P") (class "Default")
      (node (ref "X-EAST") (pin "55") (pinfunction "55_55") (pintype "bidirectional"))
      (node (ref "X-SOUTH") (pin "74") (pinfunction "74_74") (pintype "bidirectional"))
    )
    (net (code "82") (name "OUT18_N") (class "Default")
      (node (ref "X-SOUTH") (pin "71") (pinfunction "71_71") (pintype "bidirectional"))
    )
    (net (code "83") (name "OUT18_P") (class "Default")
      (node (ref "X-SOUTH") (pin "69") (pinfunction "69_69") (pintype "bidirectional"))
    )
    (net (code "84") (name "OUT19_N") (class "Default")
      (node (ref "X-EAST") (pin "60") (pinfunction "60_60") (pintype "bidirectional"))
      (node (ref "X-SOUTH") (pin "65") (pinfunction "65_65") (pintype "bidirectional"))
    )
    (net (code "85") (name "OUT19_P") (class "Default")
      (node (ref "X-EAST") (pin "62") (pinfunction "62_62") (pintype "bidirectional"))
      (node (ref "X-SOUTH") (pin "63") (pinfunction "63_63") (pintype "bidirectional"))
    )
    (net (code "86") (name "OUT20_N") (class "Default")
      (node (ref "X-SOUTH") (pin "70") (pinfunction "70_70") (pintype "bidirectional"))
    )
    (net (code "87") (name "OUT20_P") (class "Default")
      (node (ref "X-SOUTH") (pin "68") (pinfunction "68_68") (pintype "bidirectional"))
    )
    (net (code "88") (name "OUT21_N") (class "Default")
      (node (ref "X-EAST") (pin "59") (pinfunction "59_59") (pintype "bidirectional"))
      (node (ref "X-SOUTH") (pin "64") (pinfunction "64_64") (pintype "bidirectional"))
    )
    (net (code "89") (name "OUT21_P") (class "Default")
      (node (ref "X-EAST") (pin "61") (pinfunction "61_61") (pintype "bidirectional"))
      (node (ref "X-SOUTH") (pin "62") (pinfunction "62_62") (pintype "bidirectional"))
    )
    (net (code "90") (name "OUT22_N") (class "Default")
      (node (ref "X-SOUTH") (pin "59") (pinfunction "59_59") (pintype "bidirectional"))
    )
    (net (code "91") (name "OUT22_P") (class "Default")
      (node (ref "X-SOUTH") (pin "57") (pinfunction "57_57") (pintype "bidirectional"))
    )
    (net (code "92") (name "OUT23_N") (class "Default")
      (node (ref "X-EAST") (pin "66") (pinfunction "66_66") (pintype "bidirectional"))
      (node (ref "X-SOUTH") (pin "53") (pinfunction "53_53") (pintype "bidirectional"))
    )
    (net (code "93") (name "OUT23_P") (class "Default")
      (node (ref "X-EAST") (pin "68") (pinfunction "68_68") (pintype "bidirectional"))
      (node (ref "X-SOUTH") (pin "51") (pinfunction "51_51") (pintype "bidirectional"))
    )
    (net (code "94") (name "OUT24_N") (class "Default")
      (node (ref "X-SOUTH") (pin "52") (pinfunction "52_52") (pintype "bidirectional"))
    )
    (net (code "95") (name "OUT24_P") (class "Default")
      (node (ref "X-SOUTH") (pin "50") (pinfunction "50_50") (pintype "bidirectional"))
    )
    (net (code "96") (name "OUT25_N") (class "Default")
      (node (ref "X-EAST") (pin "65") (pinfunction "65_65") (pintype "bidirectional"))
      (node (ref "X-SOUTH") (pin "58") (pinfunction "58_58") (pintype "bidirectional"))
    )
    (net (code "97") (name "OUT25_P") (class "Default")
      (node (ref "X-EAST") (pin "67") (pinfunction "67_67") (pintype "bidirectional"))
      (node (ref "X-SOUTH") (pin "56") (pinfunction "56_56") (pintype "bidirectional"))
    )
    (net (code "98") (name "OUT26_N") (class "Default")
      (node (ref "X-SOUTH") (pin "47") (pinfunction "47_47") (pintype "bidirectional"))
    )
    (net (code "99") (name "OUT26_P") (class "Default")
      (node (ref "X-SOUTH") (pin "45") (pinfunction "45_45") (pintype "bidirectional"))
    )
    (net (code "100") (name "OUT27_N") (class "Default")
      (node (ref "X-EAST") (pin "73") (pinfunction "73_73") (pintype "bidirectional"))
      (node (ref "X-SOUTH") (pin "40") (pinfunction "40_40") (pintype "bidirectional"))
    )
    (net (code "101") (name "OUT27_P") (class "Default")
      (node (ref "X-EAST") (pin "75") (pinfunction "75_75") (pintype "bidirectional"))
      (node (ref "X-SOUTH") (pin "38") (pinfunction "38_38") (pintype "bidirectional"))
    )
    (net (code "102") (name "OUT28_N") (class "Default")
      (node (ref "X-SOUTH") (pin "46") (pinfunction "46_46") (pintype "bidirectional"))
    )
    (net (code "103") (name "OUT28_P") (class "Default")
      (node (ref "X-SOUTH") (pin "44") (pinfunction "44_44") (pintype "bidirectional"))
    )
    (net (code "104") (name "OUT29_N") (class "Default")
      (node (ref "X-EAST") (pin "72") (pinfunction "72_72") (pintype "bidirectional"))
      (node (ref "X-SOUTH") (pin "41") (pinfunction "41_41") (pintype "bidirectional"))
    )
    (net (code "105") (name "OUT29_P") (class "Default")
      (node (ref "X-EAST") (pin "74") (pinfunction "74_74") (pintype "bidirectional"))
      (node (ref "X-SOUTH") (pin "39") (pinfunction "39_39") (pintype "bidirectional"))
    )
    (net (code "106") (name "OUT30_N") (class "Default")
      (node (ref "X-SOUTH") (pin "34") (pinfunction "34_34") (pintype "bidirectional"))
    )
    (net (code "107") (name "OUT30_P") (class "Default")
      (node (ref "X-SOUTH") (pin "32") (pinfunction "32_32") (pintype "bidirectional"))
    )
    (net (code "108") (name "OUT31_N") (class "Default")
      (node (ref "X-EAST") (pin "78") (pinfunction "78_78") (pintype "bidirectional"))
      (node (ref "X-SOUTH") (pin "35") (pinfunction "35_35") (pintype "bidirectional"))
    )
    (net (code "109") (name "OUT31_P") (class "Default")
      (node (ref "X-EAST") (pin "80") (pinfunction "80_80") (pintype "bidirectional"))
      (node (ref "X-SOUTH") (pin "33") (pinfunction "33_33") (pintype "bidirectional"))
    )
    (net (code "110") (name "OUT32_N") (class "Default")
      (node (ref "X-SOUTH") (pin "28") (pinfunction "28_28") (pintype "bidirectional"))
    )
    (net (code "111") (name "OUT32_P") (class "Default")
      (node (ref "X-SOUTH") (pin "26") (pinfunction "26_26") (pintype "bidirectional"))
    )
    (net (code "112") (name "OUT33_N") (class "Default")
      (node (ref "X-NORTH") (pin "20") (pinfunction "20_20") (pintype "bidirectional"))
      (node (ref "X-WEST") (pin "67") (pinfunction "67_67") (pintype "bidirectional"))
    )
    (net (code "113") (name "OUT33_P") (class "Default")
      (node (ref "X-NORTH") (pin "22") (pinfunction "22_22") (pintype "bidirectional"))
      (node (ref "X-WEST") (pin "65") (pinfunction "65_65") (pintype "bidirectional"))
    )
    (net (code "114") (name "OUT34_N") (class "Default")
      (node (ref "X-NORTH") (pin "27") (pinfunction "27_27") (pintype "bidirectional"))
    )
    (net (code "115") (name "OUT34_P") (class "Default")
      (node (ref "X-NORTH") (pin "29") (pinfunction "29_29") (pintype "bidirectional"))
    )
    (net (code "116") (name "OUT35_N") (class "Default")
      (node (ref "X-NORTH") (pin "26") (pinfunction "26_26") (pintype "bidirectional"))
      (node (ref "X-WEST") (pin "61") (pinfunction "61_61") (pintype "bidirectional"))
    )
    (net (code "117") (name "OUT35_P") (class "Default")
      (node (ref "X-NORTH") (pin "28") (pinfunction "28_28") (pintype "bidirectional"))
      (node (ref "X-WEST") (pin "59") (pinfunction "59_59") (pintype "bidirectional"))
    )
    (net (code "118") (name "OUT36_N") (class "Default")
      (node (ref "X-NORTH") (pin "33") (pinfunction "33_33") (pintype "bidirectional"))
    )
    (net (code "119") (name "OUT36_P") (class "Default")
      (node (ref "X-NORTH") (pin "35") (pinfunction "35_35") (pintype "bidirectional"))
    )
    (net (code "120") (name "OUT37_N") (class "Default")
      (node (ref "X-NORTH") (pin "32") (pinfunction "32_32") (pintype "bidirectional"))
      (node (ref "X-WEST") (pin "47") (pinfunction "47_47") (pintype "bidirectional"))
    )
    (net (code "121") (name "OUT37_P") (class "Default")
      (node (ref "X-NORTH") (pin "34") (pinfunction "34_34") (pintype "bidirectional"))
      (node (ref "X-WEST") (pin "45") (pinfunction "45_45") (pintype "bidirectional"))
    )
    (net (code "122") (name "OUT38_N") (class "Default")
      (node (ref "X-NORTH") (pin "38") (pinfunction "38_38") (pintype "bidirectional"))
    )
    (net (code "123") (name "OUT38_P") (class "Default")
      (node (ref "X-NORTH") (pin "40") (pinfunction "40_40") (pintype "bidirectional"))
    )
    (net (code "124") (name "OUT39_N") (class "Default")
      (node (ref "X-NORTH") (pin "39") (pinfunction "39_39") (pintype "bidirectional"))
      (node (ref "X-WEST") (pin "80") (pinfunction "80_80") (pintype "bidirectional"))
    )
    (net (code "125") (name "OUT39_P") (class "Default")
      (node (ref "X-NORTH") (pin "41") (pinfunction "41_41") (pintype "bidirectional"))
      (node (ref "X-WEST") (pin "78") (pinfunction "78_78") (pintype "bidirectional"))
    )
    (net (code "126") (name "OUT40_N") (class "Default")
      (node (ref "X-NORTH") (pin "44") (pinfunction "44_44") (pintype "bidirectional"))
    )
    (net (code "127") (name "OUT40_P") (class "Default")
      (node (ref "X-NORTH") (pin "46") (pinfunction "46_46") (pintype "bidirectional"))
    )
    (net (code "128") (name "OUT41_N") (class "Default")
      (node (ref "X-NORTH") (pin "45") (pinfunction "45_45") (pintype "bidirectional"))
      (node (ref "X-WEST") (pin "74") (pinfunction "74_74") (pintype "bidirectional"))
    )
    (net (code "129") (name "OUT41_P") (class "Default")
      (node (ref "X-NORTH") (pin "47") (pinfunction "47_47") (pintype "bidirectional"))
      (node (ref "X-WEST") (pin "72") (pinfunction "72_72") (pintype "bidirectional"))
    )
    (net (code "130") (name "OUT42_N") (class "Default")
      (node (ref "X-NORTH") (pin "50") (pinfunction "50_50") (pintype "bidirectional"))
    )
    (net (code "131") (name "OUT42_P") (class "Default")
      (node (ref "X-NORTH") (pin "52") (pinfunction "52_52") (pintype "bidirectional"))
    )
    (net (code "132") (name "OUT43_N") (class "Default")
      (node (ref "X-NORTH") (pin "51") (pinfunction "51_51") (pintype "bidirectional"))
      (node (ref "X-WEST") (pin "68") (pinfunction "68_68") (pintype "bidirectional"))
    )
    (net (code "133") (name "OUT43_P") (class "Default")
      (node (ref "X-NORTH") (pin "53") (pinfunction "53_53") (pintype "bidirectional"))
      (node (ref "X-WEST") (pin "66") (pinfunction "66_66") (pintype "bidirectional"))
    )
    (net (code "134") (name "OUT44_N") (class "Default")
      (node (ref "X-NORTH") (pin "56") (pinfunction "56_56") (pintype "bidirectional"))
    )
    (net (code "135") (name "OUT44_P") (class "Default")
      (node (ref "X-NORTH") (pin "58") (pinfunction "58_58") (pintype "bidirectional"))
    )
    (net (code "136") (name "OUT45_N") (class "Default")
      (node (ref "X-NORTH") (pin "57") (pinfunction "57_57") (pintype "bidirectional"))
      (node (ref "X-WEST") (pin "62") (pinfunction "62_62") (pintype "bidirectional"))
    )
    (net (code "137") (name "OUT45_P") (class "Default")
      (node (ref "X-NORTH") (pin "59") (pinfunction "59_59") (pintype "bidirectional"))
      (node (ref "X-WEST") (pin "60") (pinfunction "60_60") (pintype "bidirectional"))
    )
    (net (code "138") (name "OUT46_N") (class "Default")
      (node (ref "X-NORTH") (pin "62") (pinfunction "62_62") (pintype "bidirectional"))
    )
    (net (code "139") (name "OUT46_P") (class "Default")
      (node (ref "X-NORTH") (pin "64") (pinfunction "64_64") (pintype "bidirectional"))
    )
    (net (code "140") (name "OUT47_N") (class "Default")
      (node (ref "X-NORTH") (pin "63") (pinfunction "63_63") (pintype "bidirectional"))
      (node (ref "X-WEST") (pin "56") (pinfunction "56_56") (pintype "bidirectional"))
    )
    (net (code "141") (name "OUT47_P") (class "Default")
      (node (ref "X-NORTH") (pin "65") (pinfunction "65_65") (pintype "bidirectional"))
      (node (ref "X-WEST") (pin "54") (pinfunction "54_54") (pintype "bidirectional"))
    )
    (net (code "142") (name "OUT48_N") (class "Default")
      (node (ref "X-NORTH") (pin "68") (pinfunction "68_68") (pintype "bidirectional"))
    )
    (net (code "143") (name "OUT48_P") (class "Default")
      (node (ref "X-NORTH") (pin "70") (pinfunction "70_70") (pintype "bidirectional"))
    )
    (net (code "144") (name "OUT49_N") (class "Default")
      (node (ref "X-EAST") (pin "48") (pinfunction "48_48") (pintype "bidirectional"))
      (node (ref "X-NORTH") (pin "74") (pinfunction "74_74") (pintype "bidirectional"))
    )
    (net (code "145") (name "OUT49_P") (class "Default")
      (node (ref "X-EAST") (pin "46") (pinfunction "46_46") (pintype "bidirectional"))
      (node (ref "X-NORTH") (pin "76") (pinfunction "76_76") (pintype "bidirectional"))
    )
    (net (code "146") (name "OUT50_N") (class "Default")
      (node (ref "X-NORTH") (pin "69") (pinfunction "69_69") (pintype "bidirectional"))
    )
    (net (code "147") (name "OUT50_P") (class "Default")
      (node (ref "X-NORTH") (pin "71") (pinfunction "71_71") (pintype "bidirectional"))
    )
    (net (code "148") (name "OUT51_N") (class "Default")
      (node (ref "X-EAST") (pin "42") (pinfunction "42_42") (pintype "bidirectional"))
      (node (ref "X-NORTH") (pin "80") (pinfunction "80_80") (pintype "bidirectional"))
    )
    (net (code "149") (name "OUT51_P") (class "Default")
      (node (ref "X-EAST") (pin "40") (pinfunction "40_40") (pintype "bidirectional"))
      (node (ref "X-NORTH") (pin "82") (pinfunction "82_82") (pintype "bidirectional"))
    )
    (net (code "150") (name "OUT52_N") (class "Default")
      (node (ref "X-NORTH") (pin "75") (pinfunction "75_75") (pintype "bidirectional"))
    )
    (net (code "151") (name "OUT52_P") (class "Default")
      (node (ref "X-NORTH") (pin "77") (pinfunction "77_77") (pintype "bidirectional"))
    )
    (net (code "152") (name "OUT53_N") (class "Default")
      (node (ref "X-EAST") (pin "47") (pinfunction "47_47") (pintype "bidirectional"))
      (node (ref "X-NORTH") (pin "86") (pinfunction "86_86") (pintype "bidirectional"))
    )
    (net (code "153") (name "OUT53_P") (class "Default")
      (node (ref "X-EAST") (pin "45") (pinfunction "45_45") (pintype "bidirectional"))
      (node (ref "X-NORTH") (pin "88") (pinfunction "88_88") (pintype "bidirectional"))
    )
    (net (code "154") (name "OUT54_N") (class "Default")
      (node (ref "X-NORTH") (pin "81") (pinfunction "81_81") (pintype "bidirectional"))
    )
    (net (code "155") (name "OUT54_P") (class "Default")
      (node (ref "X-NORTH") (pin "83") (pinfunction "83_83") (pintype "bidirectional"))
    )
    (net (code "156") (name "OUT55_N") (class "Default")
      (node (ref "X-EAST") (pin "41") (pinfunction "41_41") (pintype "bidirectional"))
      (node (ref "X-NORTH") (pin "92") (pinfunction "92_92") (pintype "bidirectional"))
    )
    (net (code "157") (name "OUT55_P") (class "Default")
      (node (ref "X-EAST") (pin "39") (pinfunction "39_39") (pintype "bidirectional"))
      (node (ref "X-NORTH") (pin "94") (pinfunction "94_94") (pintype "bidirectional"))
    )
    (net (code "158") (name "OUT56_N") (class "Default")
      (node (ref "X-NORTH") (pin "87") (pinfunction "87_87") (pintype "bidirectional"))
    )
    (net (code "159") (name "OUT56_P") (class "Default")
      (node (ref "X-NORTH") (pin "89") (pinfunction "89_89") (pintype "bidirectional"))
    )
    (net (code "160") (name "OUT57_N") (class "Default")
      (node (ref "X-EAST") (pin "35") (pinfunction "35_35") (pintype "bidirectional"))
      (node (ref "X-NORTH") (pin "98") (pinfunction "98_98") (pintype "bidirectional"))
    )
    (net (code "161") (name "OUT57_P") (class "Default")
      (node (ref "X-EAST") (pin "33") (pinfunction "33_33") (pintype "bidirectional"))
      (node (ref "X-NORTH") (pin "100") (pinfunction "100_100") (pintype "bidirectional"))
    )
    (net (code "162") (name "OUT58_N") (class "Default")
      (node (ref "X-NORTH") (pin "93") (pinfunction "93_93") (pintype "bidirectional"))
    )
    (net (code "163") (name "OUT58_P") (class "Default")
      (node (ref "X-NORTH") (pin "95") (pinfunction "95_95") (pintype "bidirectional"))
    )
    (net (code "164") (name "OUT59_N") (class "Default")
      (node (ref "X-EAST") (pin "27") (pinfunction "27_27") (pintype "bidirectional"))
      (node (ref "X-NORTH") (pin "104") (pinfunction "104_104") (pintype "bidirectional"))
    )
    (net (code "165") (name "OUT59_P") (class "Default")
      (node (ref "X-EAST") (pin "25") (pinfunction "25_25") (pintype "bidirectional"))
      (node (ref "X-NORTH") (pin "106") (pinfunction "106_106") (pintype "bidirectional"))
    )
    (net (code "166") (name "OUT60_N") (class "Default")
      (node (ref "X-NORTH") (pin "110") (pinfunction "110_110") (pintype "bidirectional"))
    )
    (net (code "167") (name "OUT60_P") (class "Default")
      (node (ref "X-NORTH") (pin "112") (pinfunction "112_112") (pintype "bidirectional"))
    )
    (net (code "168") (name "OUT61_N") (class "Default")
      (node (ref "X-EAST") (pin "36") (pinfunction "36_36") (pintype "bidirectional"))
      (node (ref "X-NORTH") (pin "99") (pinfunction "99_99") (pintype "bidirectional"))
    )
    (net (code "169") (name "OUT61_P") (class "Default")
      (node (ref "X-EAST") (pin "34") (pinfunction "34_34") (pintype "bidirectional"))
      (node (ref "X-NORTH") (pin "101") (pinfunction "101_101") (pintype "bidirectional"))
    )
    (net (code "170") (name "OUT62_N") (class "Default")
      (node (ref "X-NORTH") (pin "116") (pinfunction "116_116") (pintype "bidirectional"))
    )
    (net (code "171") (name "OUT62_P") (class "Default")
      (node (ref "X-NORTH") (pin "118") (pinfunction "118_118") (pintype "bidirectional"))
    )
    (net (code "172") (name "OUT63_N") (class "Default")
      (node (ref "X-EAST") (pin "30") (pinfunction "30_30") (pintype "bidirectional"))
      (node (ref "X-NORTH") (pin "105") (pinfunction "105_105") (pintype "bidirectional"))
    )
    (net (code "173") (name "OUT63_P") (class "Default")
      (node (ref "X-EAST") (pin "28") (pinfunction "28_28") (pintype "bidirectional"))
      (node (ref "X-NORTH") (pin "107") (pinfunction "107_107") (pintype "bidirectional"))
    )
    (net (code "174") (name "OUT64_N") (class "Default")
      (node (ref "X-NORTH") (pin "111") (pinfunction "111_111") (pintype "bidirectional"))
    )
    (net (code "175") (name "OUT64_P") (class "Default")
      (node (ref "X-NORTH") (pin "113") (pinfunction "113_113") (pintype "bidirectional"))
    )
    (net (code "176") (name "OUTCLK_N") (class "Default")
      (node (ref "X-NORTH") (pin "15") (pinfunction "15_15") (pintype "bidirectional"))
      (node (ref "X-WEST") (pin "53") (pinfunction "53_53") (pintype "bidirectional"))
    )
    (net (code "177") (name "OUTCLK_P") (class "Default")
      (node (ref "X-NORTH") (pin "17") (pinfunction "17_17") (pintype "bidirectional"))
      (node (ref "X-WEST") (pin "55") (pinfunction "55_55") (pintype "bidirectional"))
    )
    (net (code "178") (name "OUTCTR_N") (class "Default")
      (node (ref "X-SOUTH") (pin "125") (pinfunction "125_125") (pintype "bidirectional"))
      (node (ref "X-WEST") (pin "22") (pinfunction "22_22") (pintype "bidirectional"))
    )
    (net (code "179") (name "OUTCTR_P") (class "Default")
      (node (ref "X-SOUTH") (pin "123") (pinfunction "123_123") (pintype "bidirectional"))
      (node (ref "X-WEST") (pin "24") (pinfunction "24_24") (pintype "bidirectional"))
    )
    (net (code "180") (name "RES1") (class "Default")
      (node (ref "X-WEST") (pin "79") (pinfunction "79_79") (pintype "bidirectional"))
    )
    (net (code "181") (name "RES2") (class "Default")
      (node (ref "X-WEST") (pin "81") (pinfunction "81_81") (pintype "bidirectional"))
    )
    (net (code "182") (name "RES3") (class "Default")
      (node (ref "X-WEST") (pin "83") (pinfunction "83_83") (pintype "bidirectional"))
    )
    (net (code "183") (name "RES4") (class "Default")
      (node (ref "X-EAST") (pin "79") (pinfunction "79_79") (pintype "bidirectional"))
    )
    (net (code "184") (name "RES5") (class "Default")
      (node (ref "X-EAST") (pin "81") (pinfunction "81_81") (pintype "bidirectional"))
    )
    (net (code "185") (name "RES6") (class "Default")
      (node (ref "X-EAST") (pin "83") (pinfunction "83_83") (pintype "bidirectional"))
    )
    (net (code "186") (name "S00_N") (class "Default")
      (node (ref "X-SOUTH") (pin "16") (pinfunction "16_16") (pintype "bidirectional"))
    )
    (net (code "187") (name "S00_P") (class "Default")
      (node (ref "X-SOUTH") (pin "14") (pinfunction "14_14") (pintype "bidirectional"))
    )
    (net (code "188") (name "S01_N") (class "Default")
      (node (ref "X-SOUTH") (pin "17") (pinfunction "17_17") (pintype "bidirectional"))
    )
    (net (code "189") (name "S01_P") (class "Default")
      (node (ref "X-SOUTH") (pin "15") (pinfunction "15_15") (pintype "bidirectional"))
    )
    (net (code "190") (name "S02_N") (class "Default")
      (node (ref "X-SOUTH") (pin "22") (pinfunction "22_22") (pintype "bidirectional"))
    )
    (net (code "191") (name "S02_P") (class "Default")
      (node (ref "X-SOUTH") (pin "20") (pinfunction "20_20") (pintype "bidirectional"))
    )
    (net (code "192") (name "S03_N") (class "Default")
      (node (ref "X-SOUTH") (pin "23") (pinfunction "23_23") (pintype "bidirectional"))
    )
    (net (code "193") (name "S03_P") (class "Default")
      (node (ref "X-SOUTH") (pin "21") (pinfunction "21_21") (pintype "bidirectional"))
    )
    (net (code "194") (name "S05_N") (class "Default")
      (node (ref "X-SOUTH") (pin "29") (pinfunction "29_29") (pintype "bidirectional"))
    )
    (net (code "195") (name "S05_P") (class "Default")
      (node (ref "X-SOUTH") (pin "27") (pinfunction "27_27") (pintype "bidirectional"))
    )
    (net (code "196") (name "S38_N") (class "Default")
      (node (ref "X-SOUTH") (pin "130") (pinfunction "130_130") (pintype "bidirectional"))
    )
    (net (code "197") (name "S38_P") (class "Default")
      (node (ref "X-SOUTH") (pin "128") (pinfunction "128_128") (pintype "bidirectional"))
    )
    (net (code "198") (name "S39_N") (class "Default")
      (node (ref "X-SOUTH") (pin "131") (pinfunction "131_131") (pintype "bidirectional"))
    )
    (net (code "199") (name "S39_P") (class "Default")
      (node (ref "X-SOUTH") (pin "129") (pinfunction "129_129") (pintype "bidirectional"))
    )
    (net (code "200") (name "SYS_RES_N") (class "Default")
      (node (ref "X-EAST") (pin "22") (pinfunction "22_22") (pintype "bidirectional"))
      (node (ref "X-NORTH") (pin "125") (pinfunction "125_125") (pintype "bidirectional"))
    )
    (net (code "201") (name "S_CHK_EN") (class "Default")
      (node (ref "X-EAST") (pin "94") (pinfunction "94_94") (pintype "bidirectional"))
      (node (ref "X-SOUTH") (pin "8") (pinfunction "8_8") (pintype "bidirectional"))
    )
    (net (code "202") (name "S_CHK_V") (class "Default")
      (node (ref "X-EAST") (pin "92") (pinfunction "92_92") (pintype "bidirectional"))
      (node (ref "X-SOUTH") (pin "10") (pinfunction "10_10") (pintype "bidirectional"))
    )
    (net (code "203") (name "S_I2C_EN") (class "Default")
      (node (ref "X-SOUTH") (pin "137") (pinfunction "137_137") (pintype "bidirectional"))
      (node (ref "X-WEST") (pin "7") (pinfunction "7_7") (pintype "bidirectional"))
    )
    (net (code "204") (name "S_I2C_V") (class "Default")
      (node (ref "X-SOUTH") (pin "135") (pinfunction "135_135") (pintype "bidirectional"))
      (node (ref "X-WEST") (pin "9") (pinfunction "9_9") (pintype "bidirectional"))
    )
    (net (code "205") (name "S_SCK") (class "Default")
      (node (ref "X-SOUTH") (pin "144") (pinfunction "144_144") (pintype "bidirectional"))
      (node (ref "X-WEST") (pin "2") (pinfunction "2_2") (pintype "bidirectional"))
    )
    (net (code "206") (name "S_SCL") (class "Default")
      (node (ref "X-SOUTH") (pin "143") (pinfunction "143_143") (pintype "bidirectional"))
      (node (ref "X-WEST") (pin "1") (pinfunction "1_1") (pintype "bidirectional"))
    )
    (net (code "207") (name "S_SDA") (class "Default")
      (node (ref "X-SOUTH") (pin "141") (pinfunction "141_141") (pintype "bidirectional"))
      (node (ref "X-WEST") (pin "3") (pinfunction "3_3") (pintype "bidirectional"))
    )
    (net (code "208") (name "S_SDI") (class "Default")
      (node (ref "X-SOUTH") (pin "140") (pinfunction "140_140") (pintype "bidirectional"))
      (node (ref "X-WEST") (pin "6") (pinfunction "6_6") (pintype "bidirectional"))
    )
    (net (code "209") (name "S_SDO") (class "Default")
      (node (ref "X-SOUTH") (pin "142") (pinfunction "142_142") (pintype "bidirectional"))
      (node (ref "X-WEST") (pin "4") (pinfunction "4_4") (pintype "bidirectional"))
    )
    (net (code "210") (name "S_SPI_EN") (class "Default")
      (node (ref "X-SOUTH") (pin "136") (pinfunction "136_136") (pintype "bidirectional"))
      (node (ref "X-WEST") (pin "8") (pinfunction "8_8") (pintype "bidirectional"))
    )
    (net (code "211") (name "S_SPI_V") (class "Default")
      (node (ref "X-SOUTH") (pin "134") (pinfunction "134_134") (pintype "bidirectional"))
      (node (ref "X-WEST") (pin "10") (pinfunction "10_10") (pintype "bidirectional"))
    )
    (net (code "212") (name "S_VE") (class "Default")
      (node (ref "C7") (pin "1") (pinfunction "1_1") (pintype "passive"))
      (node (ref "SE") (pin "1") (pinfunction "1_1") (pintype "passive"))
      (node (ref "X-SOUTH") (pin "13") (pinfunction "13_13") (pintype "bidirectional"))
      (node (ref "X-SOUTH") (pin "19") (pinfunction "19_19") (pintype "bidirectional"))
      (node (ref "X-SOUTH") (pin "31") (pinfunction "31_31") (pintype "bidirectional"))
      (node (ref "X-SOUTH") (pin "37") (pinfunction "37_37") (pintype "bidirectional"))
    )
    (net (code "213") (name "S_VE_CV") (class "Default")
      (node (ref "X-EAST") (pin "100") (pinfunction "100_100") (pintype "bidirectional"))
      (node (ref "X-SOUTH") (pin "2") (pinfunction "2_2") (pintype "bidirectional"))
    )
    (net (code "214") (name "S_VE_OV") (class "Default")
      (node (ref "X-EAST") (pin "99") (pinfunction "99_99") (pintype "bidirectional"))
      (node (ref "X-SOUTH") (pin "1") (pinfunction "1_1") (pintype "bidirectional"))
    )
    (net (code "215") (name "S_VE_RS") (class "Default")
      (node (ref "X-EAST") (pin "84") (pinfunction "84_84") (pintype "bidirectional"))
      (node (ref "X-SOUTH") (pin "25") (pinfunction "25_25") (pintype "bidirectional"))
    )
    (net (code "216") (name "S_VE_UV") (class "Default")
      (node (ref "X-EAST") (pin "89") (pinfunction "89_89") (pintype "bidirectional"))
      (node (ref "X-SOUTH") (pin "7") (pinfunction "7_7") (pintype "bidirectional"))
    )
    (net (code "217") (name "S_VS") (class "Default")
      (node (ref "C6") (pin "1") (pinfunction "1_1") (pintype "passive"))
      (node (ref "SW") (pin "1") (pinfunction "1_1") (pintype "passive"))
      (node (ref "X-SOUTH") (pin "49") (pinfunction "49_49") (pintype "bidirectional"))
      (node (ref "X-SOUTH") (pin "55") (pinfunction "55_55") (pintype "bidirectional"))
      (node (ref "X-SOUTH") (pin "61") (pinfunction "61_61") (pintype "bidirectional"))
      (node (ref "X-SOUTH") (pin "67") (pinfunction "67_67") (pintype "bidirectional"))
      (node (ref "X-SOUTH") (pin "79") (pinfunction "79_79") (pintype "bidirectional"))
      (node (ref "X-SOUTH") (pin "85") (pinfunction "85_85") (pintype "bidirectional"))
      (node (ref "X-SOUTH") (pin "91") (pinfunction "91_91") (pintype "bidirectional"))
      (node (ref "X-SOUTH") (pin "97") (pinfunction "97_97") (pintype "bidirectional"))
    )
    (net (code "218") (name "S_VS_CV") (class "Default")
      (node (ref "X-EAST") (pin "98") (pinfunction "98_98") (pintype "bidirectional"))
      (node (ref "X-SOUTH") (pin "4") (pinfunction "4_4") (pintype "bidirectional"))
    )
    (net (code "219") (name "S_VS_OV") (class "Default")
      (node (ref "X-EAST") (pin "97") (pinfunction "97_97") (pintype "bidirectional"))
      (node (ref "X-SOUTH") (pin "3") (pinfunction "3_3") (pintype "bidirectional"))
    )
    (net (code "220") (name "S_VS_RS") (class "Default")
      (node (ref "X-EAST") (pin "86") (pinfunction "86_86") (pintype "bidirectional"))
      (node (ref "X-SOUTH") (pin "73") (pinfunction "73_73") (pintype "bidirectional"))
    )
    (net (code "221") (name "S_VS_UV") (class "Default")
      (node (ref "X-EAST") (pin "87") (pinfunction "87_87") (pintype "bidirectional"))
      (node (ref "X-SOUTH") (pin "9") (pinfunction "9_9") (pintype "bidirectional"))
    )
    (net (code "222") (name "S_VW") (class "Default")
      (node (ref "C2") (pin "1") (pinfunction "1_1") (pintype "passive"))
      (node (ref "SW") (pin "2") (pinfunction "2_2") (pintype "passive"))
      (node (ref "X-SOUTH") (pin "109") (pinfunction "109_109") (pintype "bidirectional"))
      (node (ref "X-SOUTH") (pin "115") (pinfunction "115_115") (pintype "bidirectional"))
      (node (ref "X-SOUTH") (pin "127") (pinfunction "127_127") (pintype "bidirectional"))
      (node (ref "X-SOUTH") (pin "133") (pinfunction "133_133") (pintype "bidirectional"))
    )
    (net (code "223") (name "S_VW_CV") (class "Default")
      (node (ref "X-EAST") (pin "96") (pinfunction "96_96") (pintype "bidirectional"))
      (node (ref "X-SOUTH") (pin "6") (pinfunction "6_6") (pintype "bidirectional"))
    )
    (net (code "224") (name "S_VW_OV") (class "Default")
      (node (ref "X-EAST") (pin "95") (pinfunction "95_95") (pintype "bidirectional"))
      (node (ref "X-SOUTH") (pin "5") (pinfunction "5_5") (pintype "bidirectional"))
    )
    (net (code "225") (name "S_VW_RS") (class "Default")
      (node (ref "X-EAST") (pin "88") (pinfunction "88_88") (pintype "bidirectional"))
      (node (ref "X-SOUTH") (pin "121") (pinfunction "121_121") (pintype "bidirectional"))
    )
    (net (code "226") (name "S_VW_UV") (class "Default")
      (node (ref "X-EAST") (pin "85") (pinfunction "85_85") (pintype "bidirectional"))
      (node (ref "X-SOUTH") (pin "11") (pinfunction "11_11") (pintype "bidirectional"))
    )
    (net (code "227") (name "TCK") (class "Default")
      (node (ref "X-WEST") (pin "12") (pinfunction "12_12") (pintype "bidirectional"))
    )
    (net (code "228") (name "TDI") (class "Default")
      (node (ref "X-WEST") (pin "16") (pinfunction "16_16") (pintype "bidirectional"))
    )
    (net (code "229") (name "TDIG1") (class "Default")
      (node (ref "X-EAST") (pin "18") (pinfunction "18_18") (pintype "bidirectional"))
      (node (ref "X-NORTH") (pin "123") (pinfunction "123_123") (pintype "bidirectional"))
    )
    (net (code "230") (name "TDIG2") (class "Default")
      (node (ref "X-NORTH") (pin "130") (pinfunction "130_130") (pintype "bidirectional"))
    )
    (net (code "231") (name "TDO") (class "Default")
      (node (ref "X-WEST") (pin "18") (pinfunction "18_18") (pintype "bidirectional"))
    )
    (net (code "232") (name "TMS") (class "Default")
      (node (ref "X-WEST") (pin "14") (pinfunction "14_14") (pintype "bidirectional"))
    )
    (net (code "233") (name "TP9") (class "Default")
      (node (ref "X-NORTH") (pin "119") (pinfunction "119_119") (pintype "bidirectional"))
    )
    (net (code "234") (name "T_EXP1") (class "Default")
      (node (ref "X-EAST") (pin "12") (pinfunction "12_12") (pintype "bidirectional"))
      (node (ref "X-NORTH") (pin "131") (pinfunction "131_131") (pintype "bidirectional"))
    )
    (net (code "235") (name "T_EXP2") (class "Default")
      (node (ref "X-EAST") (pin "16") (pinfunction "16_16") (pintype "bidirectional"))
      (node (ref "X-NORTH") (pin "117") (pinfunction "117_117") (pintype "bidirectional"))
    )
    (net (code "236") (name "W_EN") (class "Default")
      (node (ref "X-WEST") (pin "19") (pinfunction "19_19") (pintype "bidirectional"))
    )
    (net (code "237") (name "W_I2C_EN") (class "Default")
      (node (ref "X-WEST") (pin "13") (pinfunction "13_13") (pintype "bidirectional"))
    )
    (net (code "238") (name "W_I2C_V") (class "Default")
      (node (ref "X-WEST") (pin "11") (pinfunction "11_11") (pintype "bidirectional"))
    )
    (net (code "239") (name "W_SCL") (class "Default")
      (node (ref "X-WEST") (pin "15") (pinfunction "15_15") (pintype "bidirectional"))
    )
    (net (code "240") (name "W_SDA") (class "Default")
      (node (ref "X-WEST") (pin "17") (pinfunction "17_17") (pintype "bidirectional"))
    )
    (net (code "241") (name "W_VW") (class "Default")
      (node (ref "C8") (pin "1") (pinfunction "1_1") (pintype "passive"))
      (node (ref "NW") (pin "2") (pinfunction "2_2") (pintype "passive"))
    )
    (net (code "242") (name "W_VW_CV") (class "Default")
      (node (ref "X-WEST") (pin "90") (pinfunction "90_90") (pintype "bidirectional"))
    )
    (net (code "243") (name "W_VW_OV") (class "Default")
      (node (ref "X-WEST") (pin "93") (pinfunction "93_93") (pintype "bidirectional"))
    )
    (net (code "244") (name "W_VW_UV") (class "Default")
      (node (ref "X-WEST") (pin "91") (pinfunction "91_91") (pintype "bidirectional"))
    )
    (net (code "245") (name "unconnected-(X-EAST-PadM1)") (class "Default")
      (node (ref "X-EAST") (pin "M1") (pinfunction "M1_M1") (pintype "bidirectional"))
    )
    (net (code "246") (name "unconnected-(X-EAST-PadM2)") (class "Default")
      (node (ref "X-EAST") (pin "M2") (pinfunction "M2_M2") (pintype "bidirectional"))
    )
    (net (code "247") (name "unconnected-(X-NORTH-PadM1)") (class "Default")
      (node (ref "X-NORTH") (pin "M1") (pinfunction "M1_M1") (pintype "bidirectional"))
    )
    (net (code "248") (name "unconnected-(X-NORTH-PadM2)") (class "Default")
      (node (ref "X-NORTH") (pin "M2") (pinfunction "M2_M2") (pintype "bidirectional"))
    )
    (net (code "249") (name "unconnected-(X-SOUTH-PadM1)") (class "Default")
      (node (ref "X-SOUTH") (pin "M1") (pinfunction "M1_M1") (pintype "bidirectional"))
    )
    (net (code "250") (name "unconnected-(X-SOUTH-PadM2)") (class "Default")
      (node (ref "X-SOUTH") (pin "M2") (pinfunction "M2_M2") (pintype "bidirectional"))
    )
    (net (code "251") (name "unconnected-(X-WEST-PadM1)") (class "Default")
      (node (ref "X-WEST") (pin "M1") (pinfunction "M1_M1") (pintype "bidirectional"))
    )
    (net (code "252") (name "unconnected-(X-WEST-PadM2)") (class "Default")
      (node (ref "X-WEST") (pin "M2") (pinfunction "M2_M2") (pintype "bidirectional"))
    )
  )
)
